# FPGA_0.net
KiCad netlist of a schematic drawn in Altium Designer
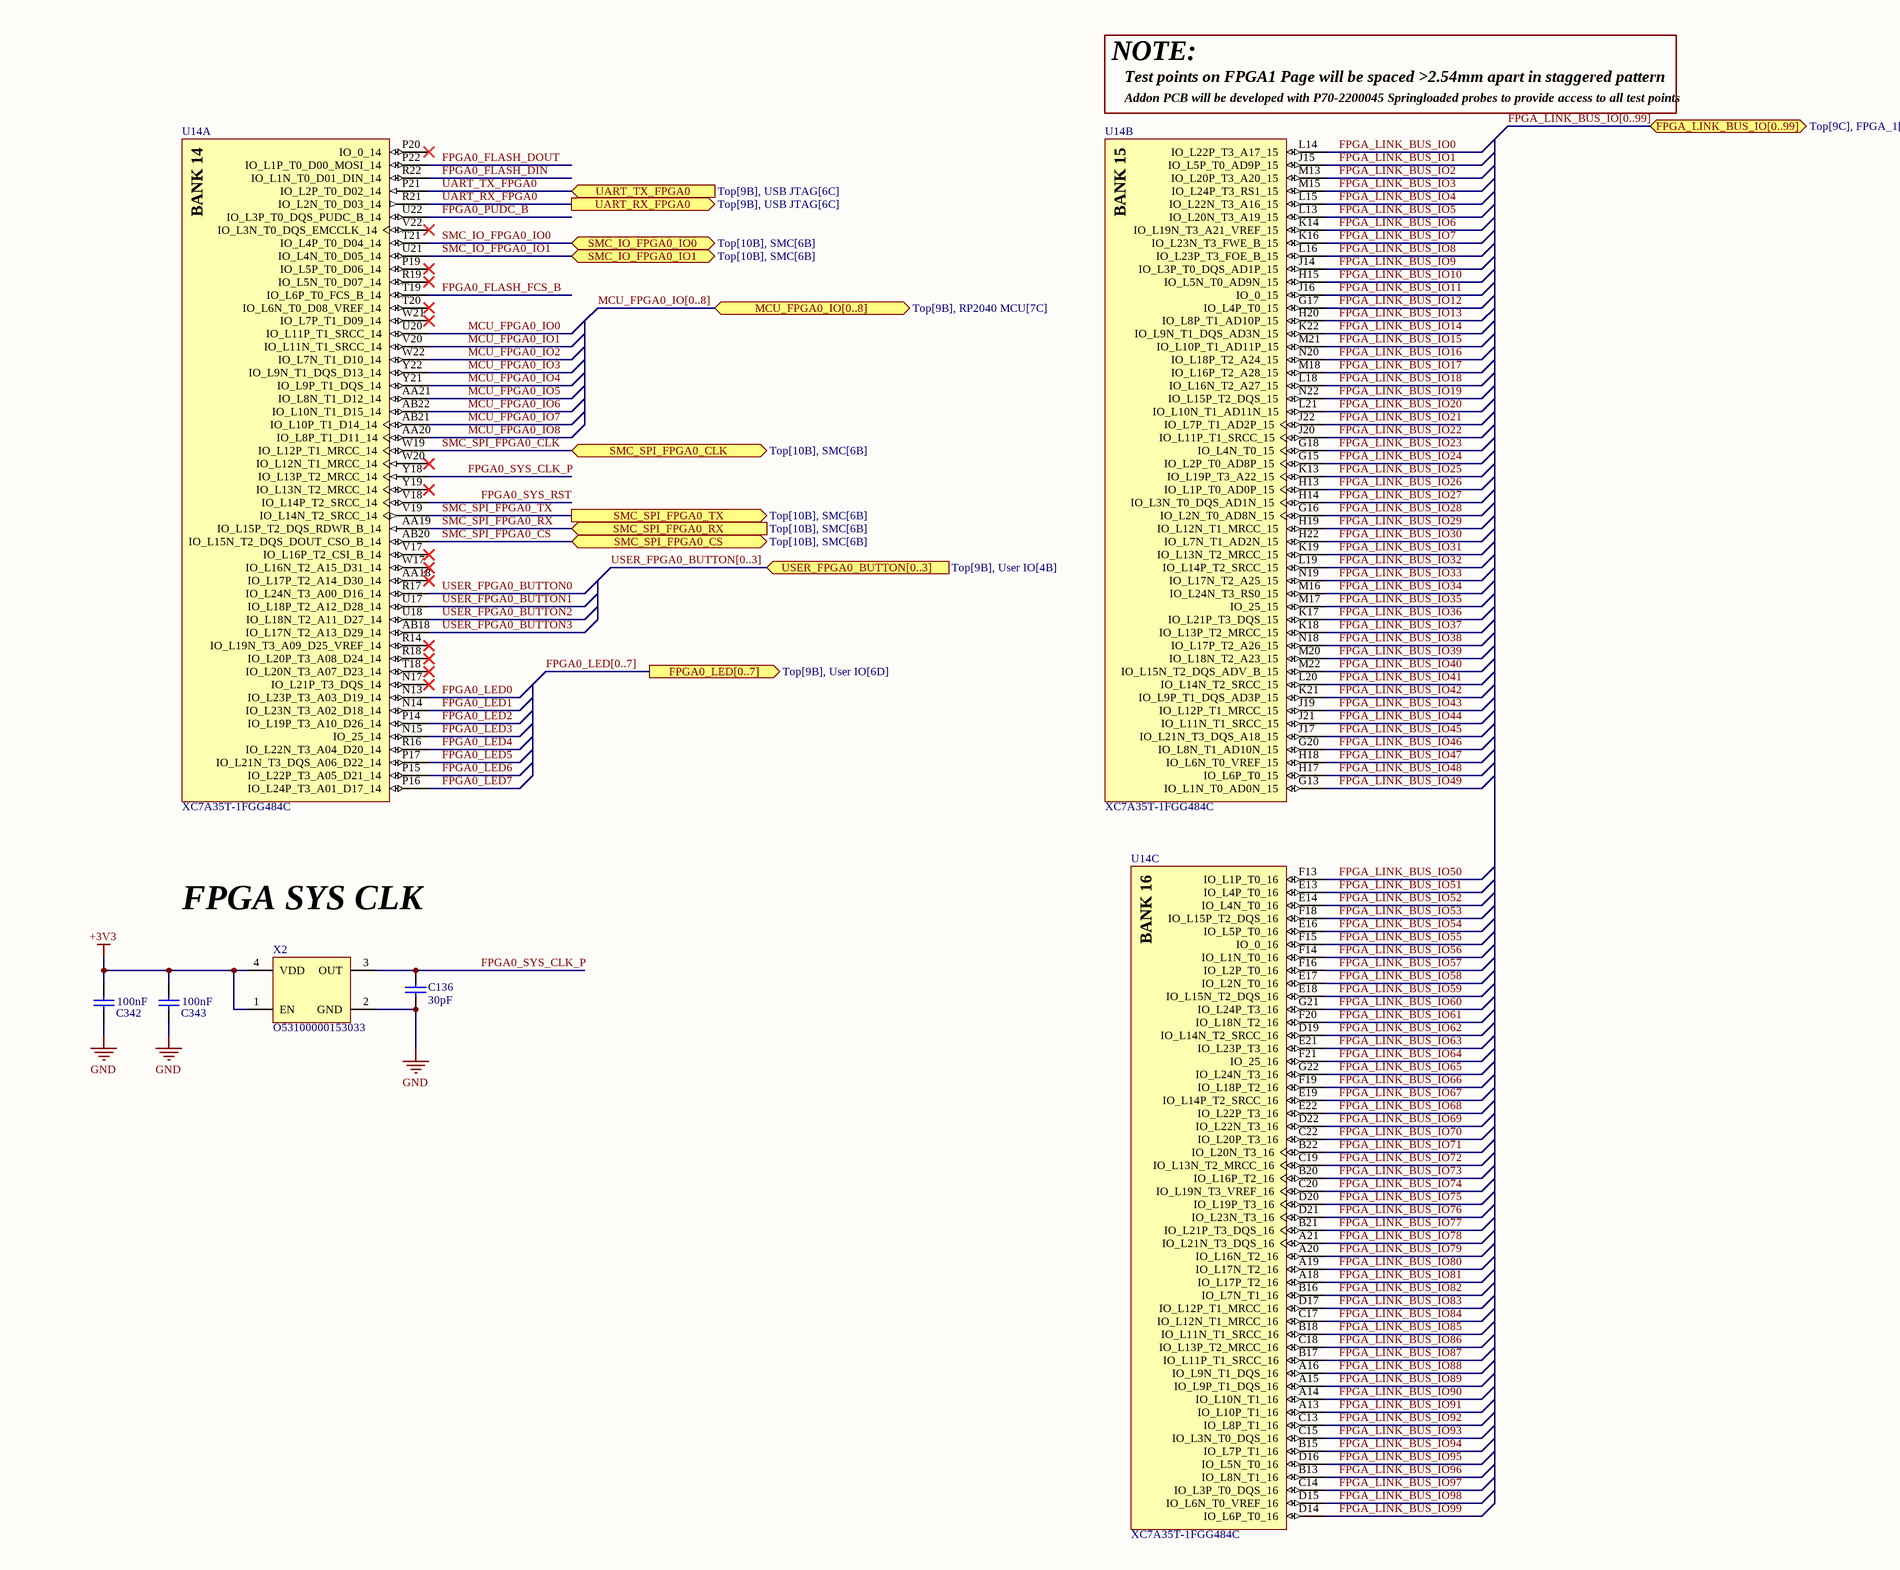
[diagram p0: FPGA_0.SchDoc, top left]
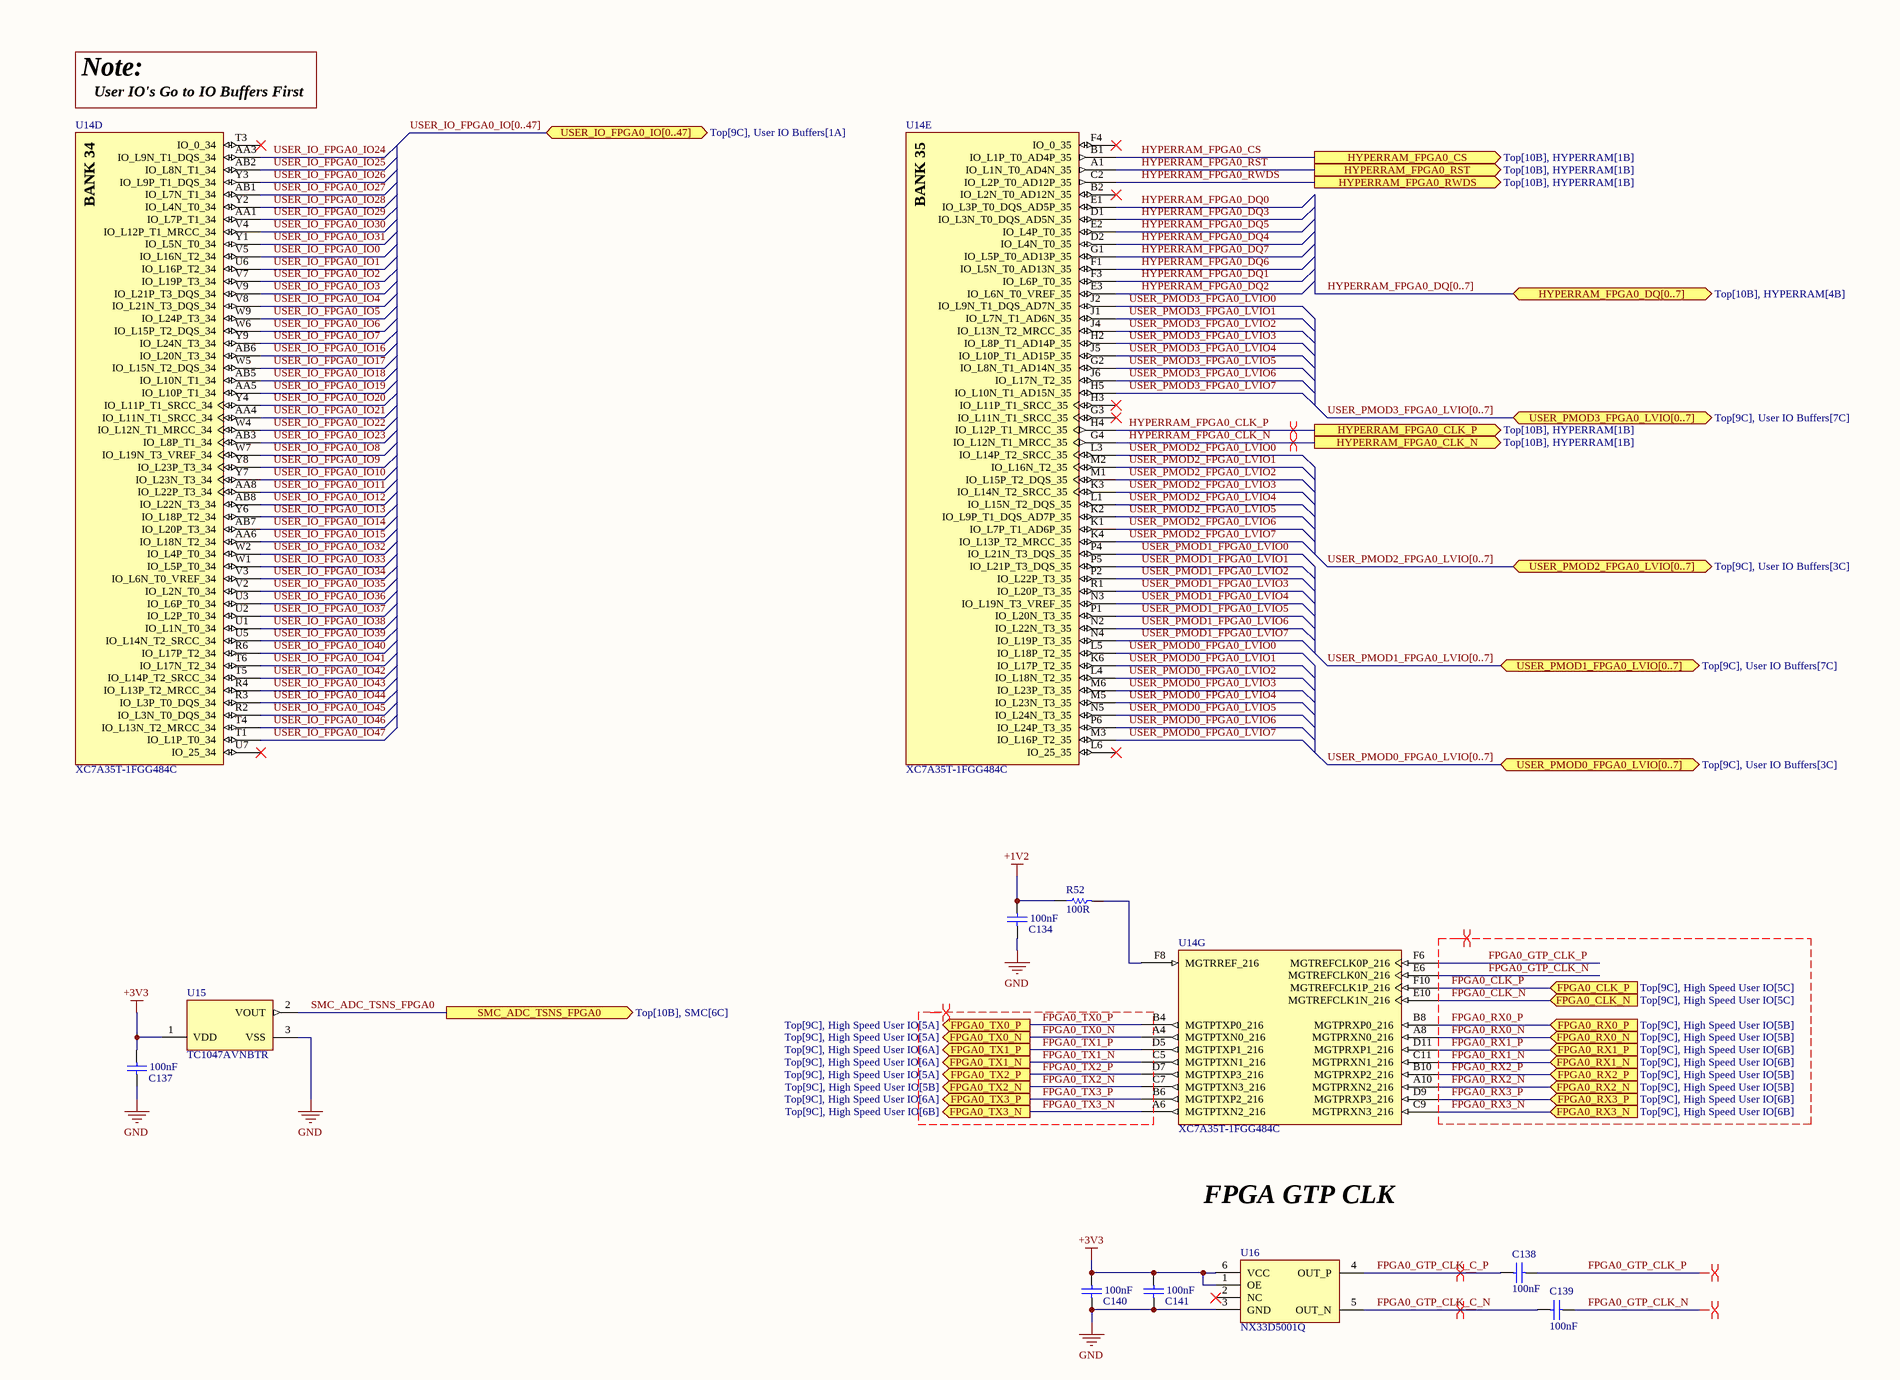
[diagram p1: FPGA_0.SchDoc, top right]
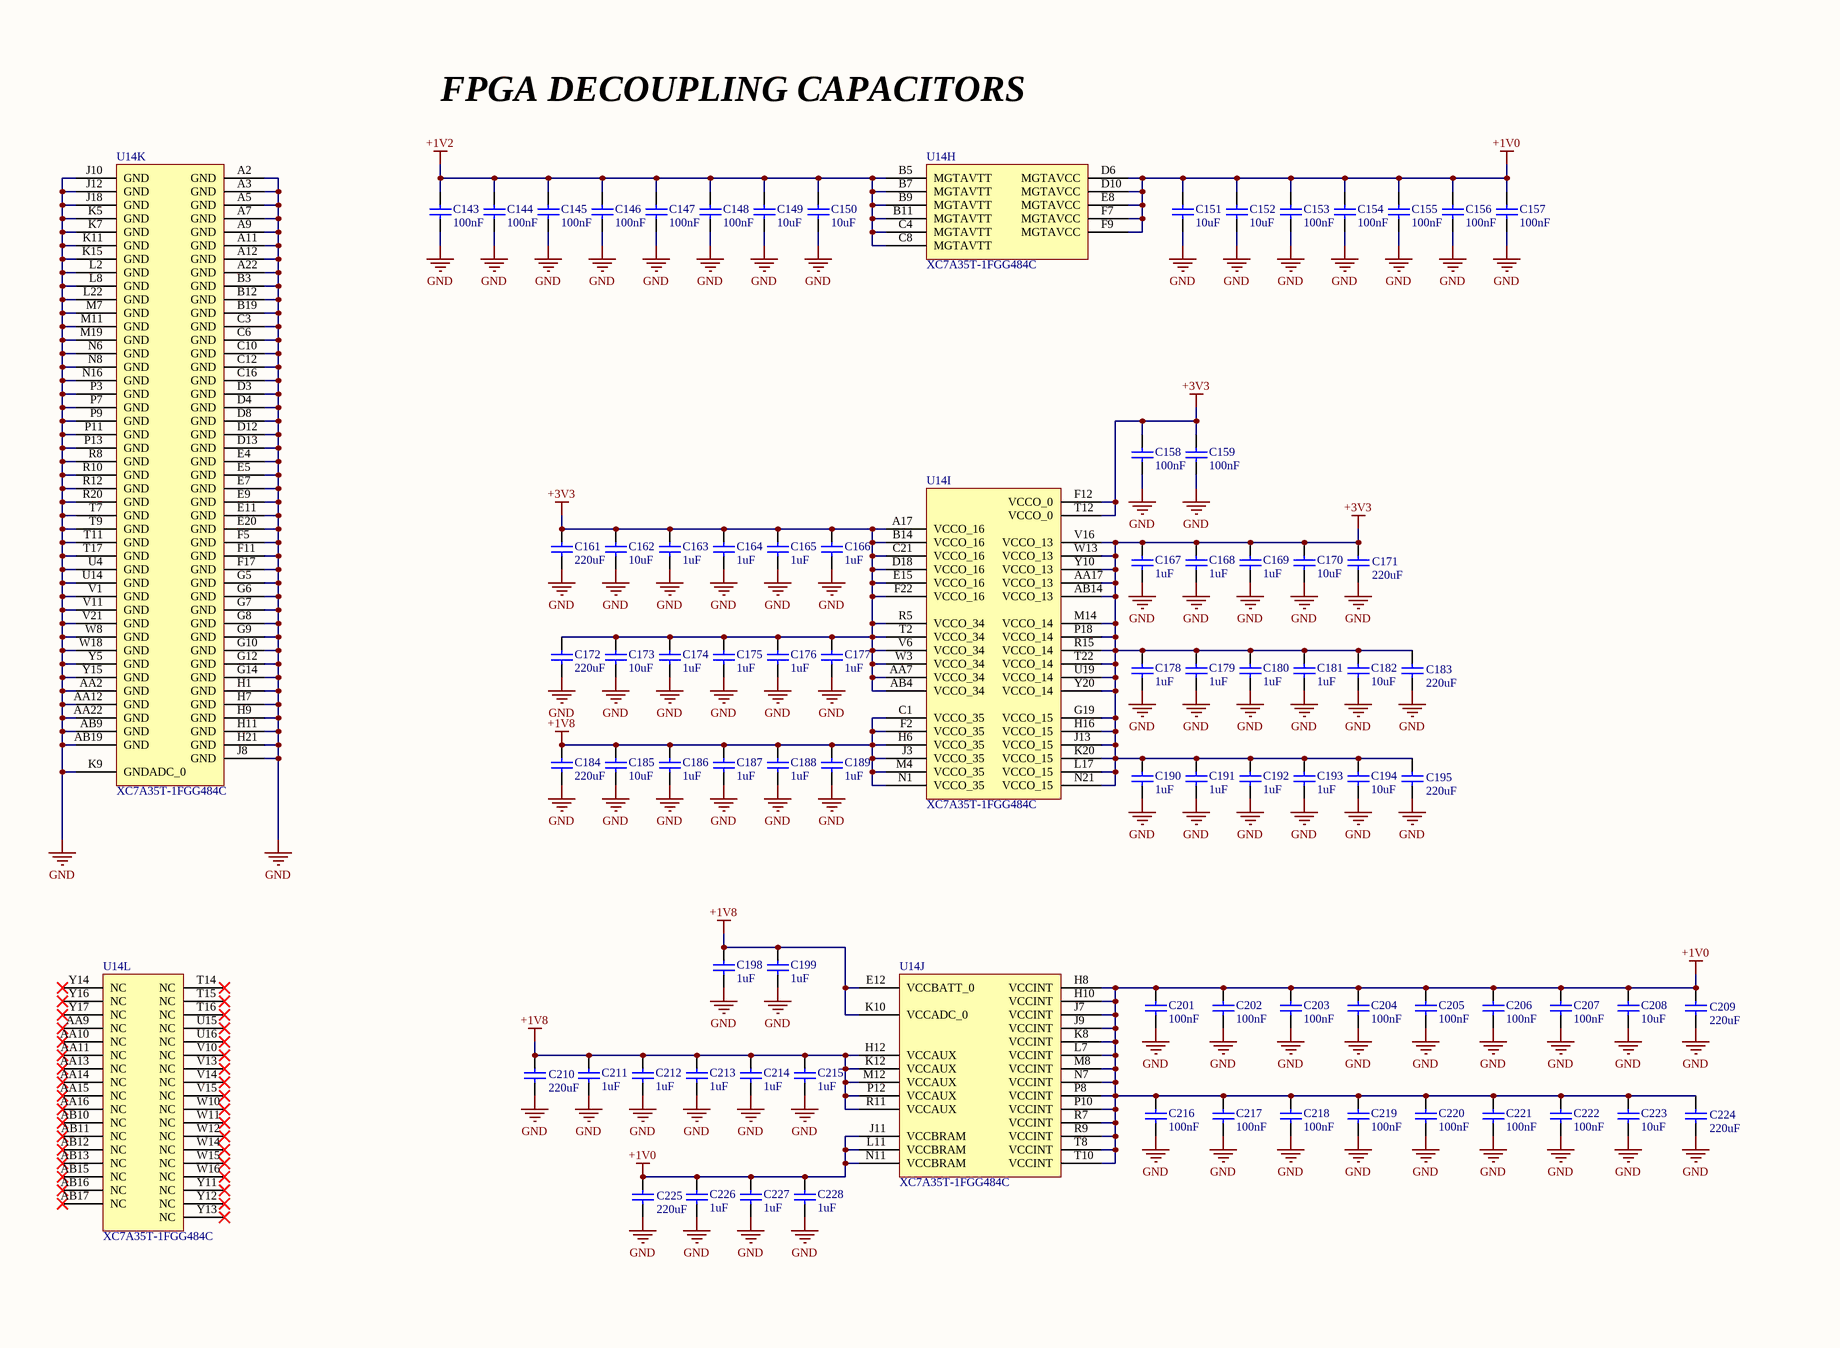
[diagram p2: FPGA_0.SchDoc, bottom left]
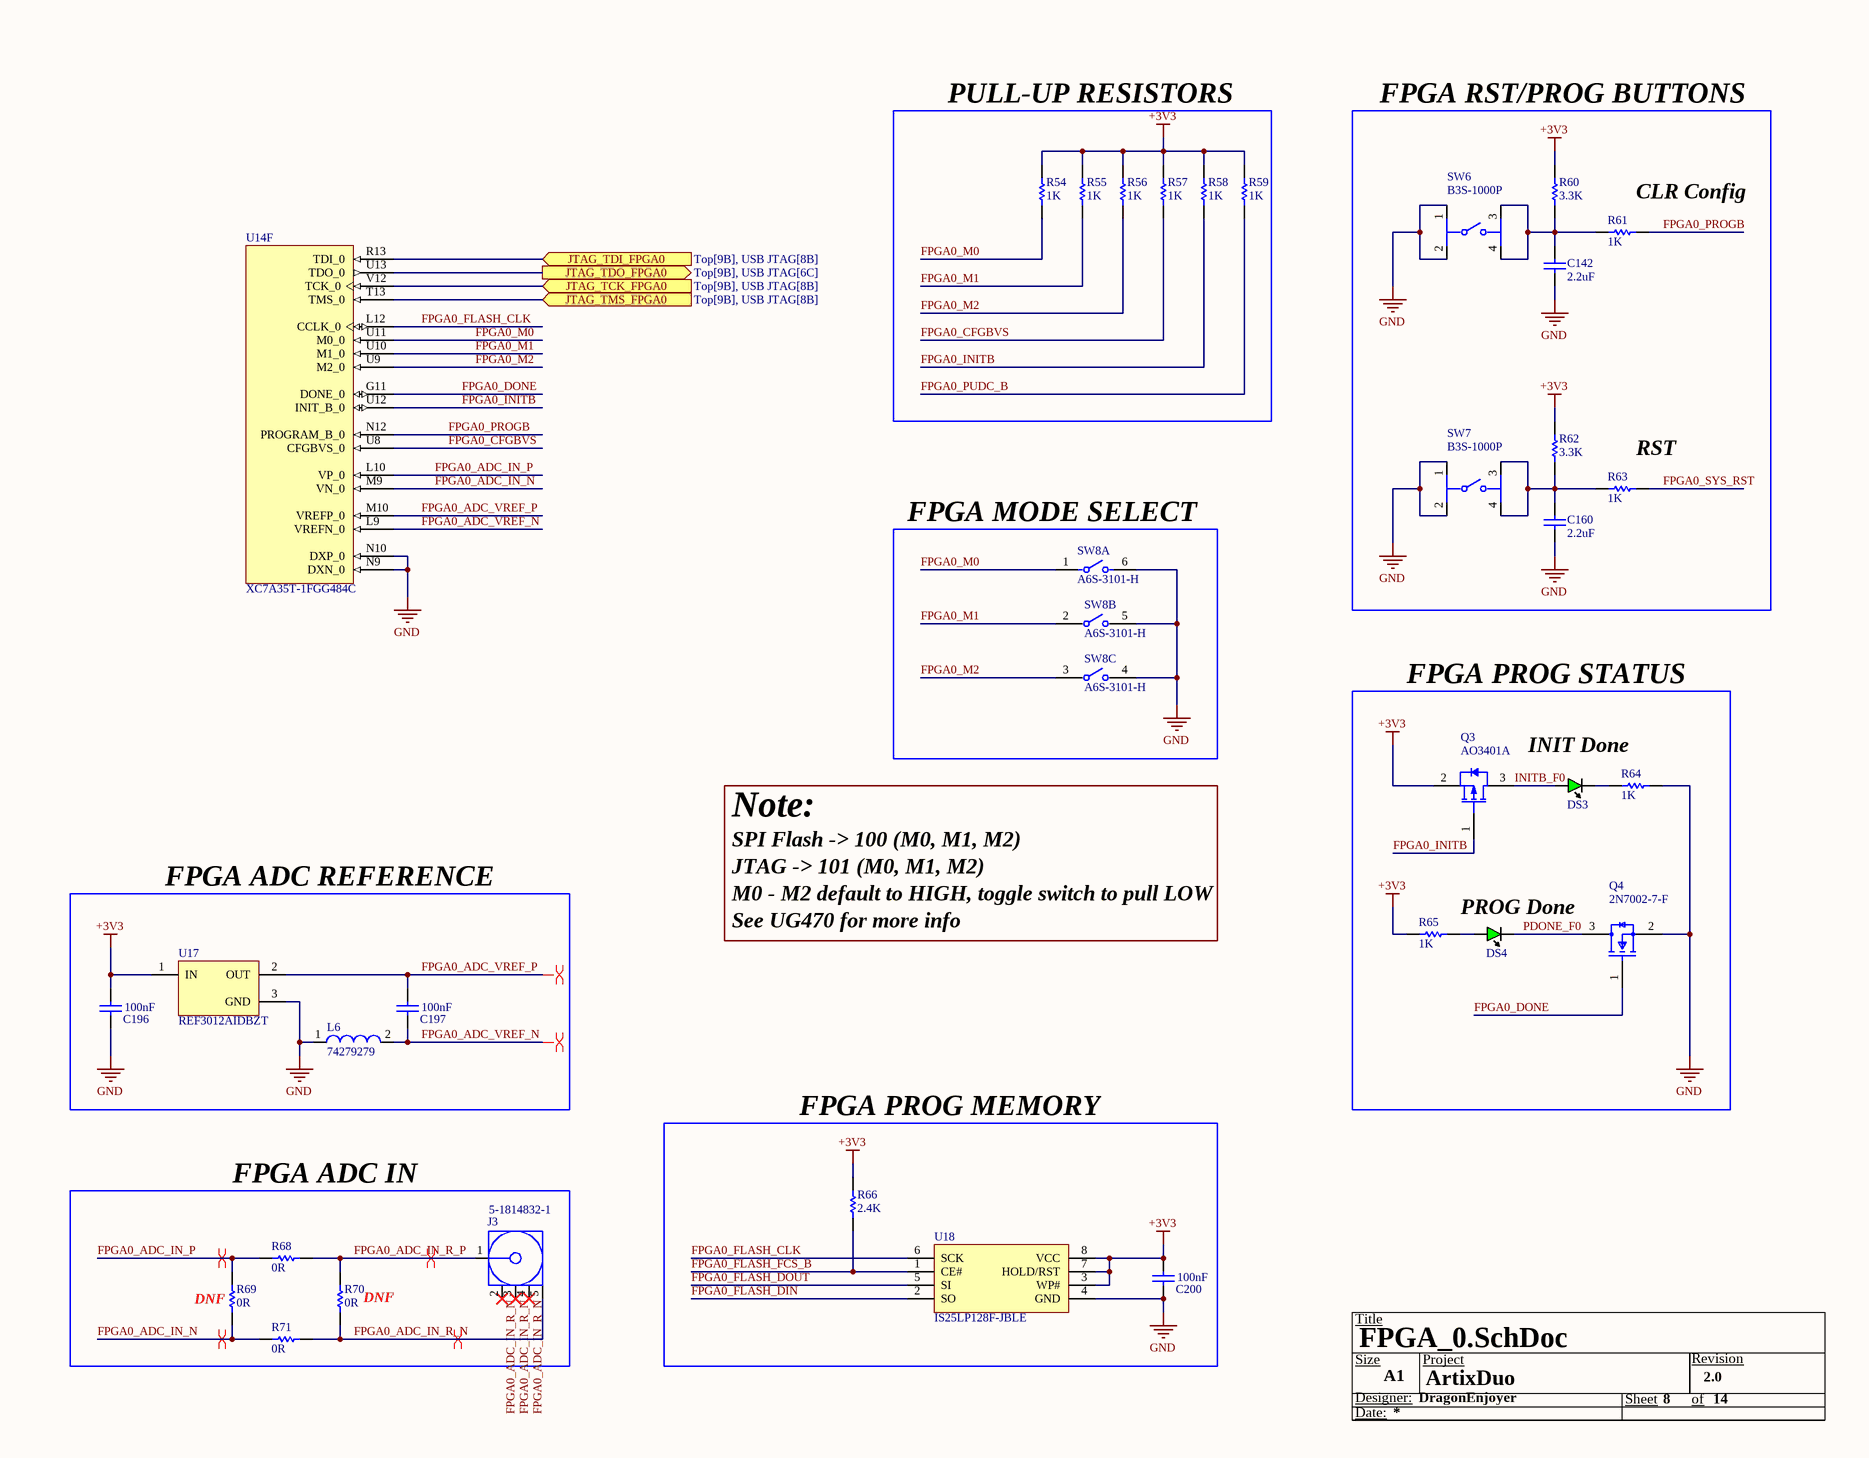
[diagram p3: FPGA_0.SchDoc, bottom right]

(export (version "E")
  (design (tool "Eeschema 10.0.6"))
  (components
    (comp (ref "C134")
      (value "100nF")
      (footprint "CAPC1005X05N")
      (description "Cap Ceramic 0.1uF 50V X7R 20% SMD 0402 125°C Paper T/R GRM155R71H104ME14J")
      (fields (field (name "VOLTAGE") "50V"))
      (libsource (lib "Main Workspace") (part "CAP"))
    )
    (comp (ref "C136")
      (value "30pF")
      (footprint "CAPC1005X56X25NL10T15")
      (description "04025A300JAT2A")
      (fields (field (name "MANUFACTURER") "AVX Interconnect / Elco"))
      (libsource (lib "Altium Content Vault") (part "CAP"))
    )
    (comp (ref "C137")
      (value "100nF")
      (footprint "CAPC1005X05N")
      (description "Cap Ceramic 0.1uF 50V X7R 20% SMD 0402 125°C Paper T/R GRM155R71H104ME14J")
      (fields (field (name "VOLTAGE") "50V"))
      (libsource (lib "Main Workspace") (part "CAP"))
    )
    (comp (ref "C138")
      (value "100nF")
      (footprint "CAPC1005X05N")
      (description "Cap Ceramic 0.1uF 50V X7R 20% SMD 0402 125°C Paper T/R GRM155R71H104ME14J")
      (fields (field (name "VOLTAGE") "50V"))
      (libsource (lib "Main Workspace") (part "CAP"))
    )
    (comp (ref "C139")
      (value "100nF")
      (footprint "CAPC1005X05N")
      (description "Cap Ceramic 0.1uF 50V X7R 20% SMD 0402 125°C Paper T/R GRM155R71H104ME14J")
      (fields (field (name "VOLTAGE") "50V"))
      (libsource (lib "Main Workspace") (part "CAP"))
    )
    (comp (ref "C140")
      (value "100nF")
      (footprint "CAPC1005X05N")
      (description "Cap Ceramic 0.1uF 50V X7R 20% SMD 0402 125°C Paper T/R GRM155R71H104ME14J")
      (fields (field (name "VOLTAGE") "50V"))
      (libsource (lib "Main Workspace") (part "CAP"))
    )
    (comp (ref "C141")
      (value "100nF")
      (footprint "CAPC1005X05N")
      (description "Cap Ceramic 0.1uF 50V X7R 20% SMD 0402 125°C Paper T/R GRM155R71H104ME14J")
      (fields (field (name "VOLTAGE") "50V"))
      (libsource (lib "Main Workspace") (part "CAP"))
    )
    (comp (ref "C142")
      (value "2.2uF")
      (footprint "CAPC1005X55X25NL05T10")
      (description "GRM155R60J225ME15D")
      (fields (field (name "MANUFACTURER") "Murata"))
      (libsource (lib "Altium Content Vault") (part "CAP"))
    )
    (comp (ref "C143")
      (value "100nF")
      (footprint "CAPC1005X05N")
      (description "0402 0.1 uF 25 V ±10% Tolerance X7R SMT Multilayer Ceramic Capacitor")
      (fields (field (name "TOLERANCE") "10%") (field (name "Comment") "GRM155R71E104KE14J"))
      (libsource (lib "Main Workspace") (part "CAP"))
    )
    (comp (ref "C144")
      (value "100nF")
      (footprint "CAPC1005X05N")
      (description "0402 0.1 uF 25 V ±10% Tolerance X7R SMT Multilayer Ceramic Capacitor")
      (fields (field (name "TOLERANCE") "10%") (field (name "Comment") "GRM155R71E104KE14J"))
      (libsource (lib "Main Workspace") (part "CAP"))
    )
    (comp (ref "C145")
      (value "100nF")
      (footprint "CAPC1005X05N")
      (description "0402 0.1 uF 25 V ±10% Tolerance X7R SMT Multilayer Ceramic Capacitor")
      (fields (field (name "TOLERANCE") "10%") (field (name "Comment") "GRM155R71E104KE14J"))
      (libsource (lib "Main Workspace") (part "CAP"))
    )
    (comp (ref "C146")
      (value "100nF")
      (footprint "CAPC1005X05N")
      (description "0402 0.1 uF 25 V ±10% Tolerance X7R SMT Multilayer Ceramic Capacitor")
      (fields (field (name "TOLERANCE") "10%") (field (name "Comment") "GRM155R71E104KE14J"))
      (libsource (lib "Main Workspace") (part "CAP"))
    )
    (comp (ref "C147")
      (value "100nF")
      (footprint "CAPC1005X05N")
      (description "0402 0.1 uF 25 V ±10% Tolerance X7R SMT Multilayer Ceramic Capacitor")
      (fields (field (name "TOLERANCE") "10%") (field (name "Comment") "GRM155R71E104KE14J"))
      (libsource (lib "Main Workspace") (part "CAP"))
    )
    (comp (ref "C148")
      (value "100nF")
      (footprint "CAPC1005X05N")
      (description "0402 0.1 uF 25 V ±10% Tolerance X7R SMT Multilayer Ceramic Capacitor")
      (fields (field (name "TOLERANCE") "10%") (field (name "Comment") "GRM155R71E104KE14J"))
      (libsource (lib "Main Workspace") (part "CAP"))
    )
    (comp (ref "C149")
      (value "10uF")
      (footprint "CAPC1608X05N")
      (description "Cap 10UF 6.3VDC X5R 20% SMD 0603 Paper Tape")
      (fields (field (name "TOLERANCE") "20%") (field (name "Comment") "GRM185R60J106ME15J"))
      (libsource (lib "Main Workspace") (part "CAP"))
    )
    (comp (ref "C150")
      (value "10uF")
      (footprint "CAPC1608X05N")
      (description "Cap 10UF 6.3VDC X5R 20% SMD 0603 Paper Tape")
      (fields (field (name "TOLERANCE") "20%") (field (name "Comment") "GRM185R60J106ME15J"))
      (libsource (lib "Main Workspace") (part "CAP"))
    )
    (comp (ref "C151")
      (value "10uF")
      (footprint "CAPC1608X05N")
      (description "Cap 10UF 6.3VDC X5R 20% SMD 0603 Paper Tape")
      (fields (field (name "TOLERANCE") "20%") (field (name "Comment") "GRM185R60J106ME15J"))
      (libsource (lib "Main Workspace") (part "CAP"))
    )
    (comp (ref "C152")
      (value "10uF")
      (footprint "CAPC1608X05N")
      (description "Cap 10UF 6.3VDC X5R 20% SMD 0603 Paper Tape")
      (fields (field (name "TOLERANCE") "20%") (field (name "Comment") "GRM185R60J106ME15J"))
      (libsource (lib "Main Workspace") (part "CAP"))
    )
    (comp (ref "C153")
      (value "100nF")
      (footprint "CAPC1005X05N")
      (description "0402 0.1 uF 25 V ±10% Tolerance X7R SMT Multilayer Ceramic Capacitor")
      (fields (field (name "TOLERANCE") "10%") (field (name "Comment") "GRM155R71E104KE14J"))
      (libsource (lib "Main Workspace") (part "CAP"))
    )
    (comp (ref "C154")
      (value "100nF")
      (footprint "CAPC1005X05N")
      (description "0402 0.1 uF 25 V ±10% Tolerance X7R SMT Multilayer Ceramic Capacitor")
      (fields (field (name "TOLERANCE") "10%") (field (name "Comment") "GRM155R71E104KE14J"))
      (libsource (lib "Main Workspace") (part "CAP"))
    )
    (comp (ref "C155")
      (value "100nF")
      (footprint "CAPC1005X05N")
      (description "0402 0.1 uF 25 V ±10% Tolerance X7R SMT Multilayer Ceramic Capacitor")
      (fields (field (name "TOLERANCE") "10%") (field (name "Comment") "GRM155R71E104KE14J"))
      (libsource (lib "Main Workspace") (part "CAP"))
    )
    (comp (ref "C156")
      (value "100nF")
      (footprint "CAPC1005X05N")
      (description "0402 0.1 uF 25 V ±10% Tolerance X7R SMT Multilayer Ceramic Capacitor")
      (fields (field (name "TOLERANCE") "10%") (field (name "Comment") "GRM155R71E104KE14J"))
      (libsource (lib "Main Workspace") (part "CAP"))
    )
    (comp (ref "C157")
      (value "100nF")
      (footprint "CAPC1005X05N")
      (description "0402 0.1 uF 25 V ±10% Tolerance X7R SMT Multilayer Ceramic Capacitor")
      (fields (field (name "TOLERANCE") "10%") (field (name "Comment") "GRM155R71E104KE14J"))
      (libsource (lib "Main Workspace") (part "CAP"))
    )
    (comp (ref "C158")
      (value "100nF")
      (footprint "CAPC1005X05N")
      (description "0402 0.1 uF 25 V ±10% Tolerance X7R SMT Multilayer Ceramic Capacitor")
      (fields (field (name "TOLERANCE") "10%") (field (name "Comment") "GRM155R71E104KE14J"))
      (libsource (lib "Main Workspace") (part "CAP"))
    )
    (comp (ref "C159")
      (value "100nF")
      (footprint "CAPC1005X05N")
      (description "0402 0.1 uF 25 V ±10% Tolerance X7R SMT Multilayer Ceramic Capacitor")
      (fields (field (name "TOLERANCE") "10%") (field (name "Comment") "GRM155R71E104KE14J"))
      (libsource (lib "Main Workspace") (part "CAP"))
    )
    (comp (ref "C160")
      (value "2.2uF")
      (footprint "CAPC1005X55X25NL05T10")
      (description "GRM155R60J225ME15D")
      (fields (field (name "MANUFACTURER") "Murata"))
      (libsource (lib "Altium Content Vault") (part "CAP"))
    )
    (comp (ref "C161")
      (value "220uF")
      (footprint "CAPC3225X25N")
      (description "Cap Ceramic 220uF 6.3V X5R 20% SMD 1210 85°C Emboss T/R GRM32ER60J227ME05K")
      (libsource (lib "Main Workspace") (part "CAP"))
    )
    (comp (ref "C162")
      (value "10uF")
      (footprint "CAPC1608X05N")
      (description "Cap 10UF 6.3VDC X5R 20% SMD 0603 Paper Tape")
      (fields (field (name "TOLERANCE") "20%") (field (name "Comment") "GRM185R60J106ME15J"))
      (libsource (lib "Main Workspace") (part "CAP"))
    )
    (comp (ref "C163")
      (value "1uF")
      (footprint "CAPC1005X05N")
      (fields (field (name "TOLERANCE") "20%") (field (name "Comment") "GRM153R61A105ME95D"))
      (libsource (lib "Main Workspace") (part "CAP"))
    )
    (comp (ref "C164")
      (value "1uF")
      (footprint "CAPC1005X05N")
      (fields (field (name "TOLERANCE") "20%") (field (name "Comment") "GRM153R61A105ME95D"))
      (libsource (lib "Main Workspace") (part "CAP"))
    )
    (comp (ref "C165")
      (value "1uF")
      (footprint "CAPC1005X05N")
      (fields (field (name "TOLERANCE") "20%") (field (name "Comment") "GRM153R61A105ME95D"))
      (libsource (lib "Main Workspace") (part "CAP"))
    )
    (comp (ref "C166")
      (value "1uF")
      (footprint "CAPC1005X05N")
      (fields (field (name "TOLERANCE") "20%") (field (name "Comment") "GRM153R61A105ME95D"))
      (libsource (lib "Main Workspace") (part "CAP"))
    )
    (comp (ref "C167")
      (value "1uF")
      (footprint "CAPC1005X05N")
      (fields (field (name "TOLERANCE") "20%") (field (name "Comment") "GRM153R61A105ME95D"))
      (libsource (lib "Main Workspace") (part "CAP"))
    )
    (comp (ref "C168")
      (value "1uF")
      (footprint "CAPC1005X05N")
      (fields (field (name "TOLERANCE") "20%") (field (name "Comment") "GRM153R61A105ME95D"))
      (libsource (lib "Main Workspace") (part "CAP"))
    )
    (comp (ref "C169")
      (value "1uF")
      (footprint "CAPC1005X05N")
      (fields (field (name "TOLERANCE") "20%") (field (name "Comment") "GRM153R61A105ME95D"))
      (libsource (lib "Main Workspace") (part "CAP"))
    )
    (comp (ref "C170")
      (value "10uF")
      (footprint "CAPC1608X05N")
      (description "Cap 10UF 6.3VDC X5R 20% SMD 0603 Paper Tape")
      (fields (field (name "TOLERANCE") "20%") (field (name "Comment") "GRM185R60J106ME15J"))
      (libsource (lib "Main Workspace") (part "CAP"))
    )
    (comp (ref "C171")
      (value "220uF")
      (footprint "CAPC3225X25N")
      (description "Cap Ceramic 220uF 6.3V X5R 20% SMD 1210 85°C Emboss T/R GRM32ER60J227ME05K")
      (libsource (lib "Main Workspace") (part "CAP"))
    )
    (comp (ref "C172")
      (value "220uF")
      (footprint "CAPC3225X25N")
      (description "Cap Ceramic 220uF 6.3V X5R 20% SMD 1210 85°C Emboss T/R GRM32ER60J227ME05K")
      (libsource (lib "Main Workspace") (part "CAP"))
    )
    (comp (ref "C173")
      (value "10uF")
      (footprint "CAPC1608X05N")
      (description "Cap 10UF 6.3VDC X5R 20% SMD 0603 Paper Tape")
      (fields (field (name "TOLERANCE") "20%") (field (name "Comment") "GRM185R60J106ME15J"))
      (libsource (lib "Main Workspace") (part "CAP"))
    )
    (comp (ref "C174")
      (value "1uF")
      (footprint "CAPC1005X05N")
      (fields (field (name "TOLERANCE") "20%") (field (name "Comment") "GRM153R61A105ME95D"))
      (libsource (lib "Main Workspace") (part "CAP"))
    )
    (comp (ref "C175")
      (value "1uF")
      (footprint "CAPC1005X05N")
      (fields (field (name "TOLERANCE") "20%") (field (name "Comment") "GRM153R61A105ME95D"))
      (libsource (lib "Main Workspace") (part "CAP"))
    )
    (comp (ref "C176")
      (value "1uF")
      (footprint "CAPC1005X05N")
      (fields (field (name "TOLERANCE") "20%") (field (name "Comment") "GRM153R61A105ME95D"))
      (libsource (lib "Main Workspace") (part "CAP"))
    )
    (comp (ref "C177")
      (value "1uF")
      (footprint "CAPC1005X05N")
      (fields (field (name "TOLERANCE") "20%") (field (name "Comment") "GRM153R61A105ME95D"))
      (libsource (lib "Main Workspace") (part "CAP"))
    )
    (comp (ref "C178")
      (value "1uF")
      (footprint "CAPC1005X05N")
      (fields (field (name "TOLERANCE") "20%") (field (name "Comment") "GRM153R61A105ME95D"))
      (libsource (lib "Main Workspace") (part "CAP"))
    )
    (comp (ref "C179")
      (value "1uF")
      (footprint "CAPC1005X05N")
      (fields (field (name "TOLERANCE") "20%") (field (name "Comment") "GRM153R61A105ME95D"))
      (libsource (lib "Main Workspace") (part "CAP"))
    )
    (comp (ref "C180")
      (value "1uF")
      (footprint "CAPC1005X05N")
      (fields (field (name "TOLERANCE") "20%") (field (name "Comment") "GRM153R61A105ME95D"))
      (libsource (lib "Main Workspace") (part "CAP"))
    )
    (comp (ref "C181")
      (value "1uF")
      (footprint "CAPC1005X05N")
      (fields (field (name "TOLERANCE") "20%") (field (name "Comment") "GRM153R61A105ME95D"))
      (libsource (lib "Main Workspace") (part "CAP"))
    )
    (comp (ref "C182")
      (value "10uF")
      (footprint "CAPC1608X05N")
      (description "Cap 10UF 6.3VDC X5R 20% SMD 0603 Paper Tape")
      (fields (field (name "TOLERANCE") "20%") (field (name "Comment") "GRM185R60J106ME15J"))
      (libsource (lib "Main Workspace") (part "CAP"))
    )
    (comp (ref "C183")
      (value "220uF")
      (footprint "CAPC3225X25N")
      (description "Cap Ceramic 220uF 6.3V X5R 20% SMD 1210 85°C Emboss T/R GRM32ER60J227ME05K")
      (libsource (lib "Main Workspace") (part "CAP"))
    )
    (comp (ref "C184")
      (value "220uF")
      (footprint "CAPC3225X25N")
      (description "Cap Ceramic 220uF 6.3V X5R 20% SMD 1210 85°C Emboss T/R GRM32ER60J227ME05K")
      (libsource (lib "Main Workspace") (part "CAP"))
    )
    (comp (ref "C185")
      (value "10uF")
      (footprint "CAPC1608X05N")
      (description "Cap 10UF 6.3VDC X5R 20% SMD 0603 Paper Tape")
      (fields (field (name "TOLERANCE") "20%") (field (name "Comment") "GRM185R60J106ME15J"))
      (libsource (lib "Main Workspace") (part "CAP"))
    )
    (comp (ref "C186")
      (value "1uF")
      (footprint "CAPC1005X05N")
      (fields (field (name "TOLERANCE") "20%") (field (name "Comment") "GRM153R61A105ME95D"))
      (libsource (lib "Main Workspace") (part "CAP"))
    )
    (comp (ref "C187")
      (value "1uF")
      (footprint "CAPC1005X05N")
      (fields (field (name "TOLERANCE") "20%") (field (name "Comment") "GRM153R61A105ME95D"))
      (libsource (lib "Main Workspace") (part "CAP"))
    )
    (comp (ref "C188")
      (value "1uF")
      (footprint "CAPC1005X05N")
      (fields (field (name "TOLERANCE") "20%") (field (name "Comment") "GRM153R61A105ME95D"))
      (libsource (lib "Main Workspace") (part "CAP"))
    )
    (comp (ref "C189")
      (value "1uF")
      (footprint "CAPC1005X05N")
      (fields (field (name "TOLERANCE") "20%") (field (name "Comment") "GRM153R61A105ME95D"))
      (libsource (lib "Main Workspace") (part "CAP"))
    )
    (comp (ref "C190")
      (value "1uF")
      (footprint "CAPC1005X05N")
      (fields (field (name "TOLERANCE") "20%") (field (name "Comment") "GRM153R61A105ME95D"))
      (libsource (lib "Main Workspace") (part "CAP"))
    )
    (comp (ref "C191")
      (value "1uF")
      (footprint "CAPC1005X05N")
      (fields (field (name "TOLERANCE") "20%") (field (name "Comment") "GRM153R61A105ME95D"))
      (libsource (lib "Main Workspace") (part "CAP"))
    )
    (comp (ref "C192")
      (value "1uF")
      (footprint "CAPC1005X05N")
      (fields (field (name "TOLERANCE") "20%") (field (name "Comment") "GRM153R61A105ME95D"))
      (libsource (lib "Main Workspace") (part "CAP"))
    )
    (comp (ref "C193")
      (value "1uF")
      (footprint "CAPC1005X05N")
      (fields (field (name "TOLERANCE") "20%") (field (name "Comment") "GRM153R61A105ME95D"))
      (libsource (lib "Main Workspace") (part "CAP"))
    )
    (comp (ref "C194")
      (value "10uF")
      (footprint "CAPC1608X05N")
      (description "Cap 10UF 6.3VDC X5R 20% SMD 0603 Paper Tape")
      (fields (field (name "TOLERANCE") "20%") (field (name "Comment") "GRM185R60J106ME15J"))
      (libsource (lib "Main Workspace") (part "CAP"))
    )
    (comp (ref "C195")
      (value "220uF")
      (footprint "CAPC3225X25N")
      (description "Cap Ceramic 220uF 6.3V X5R 20% SMD 1210 85°C Emboss T/R GRM32ER60J227ME05K")
      (libsource (lib "Main Workspace") (part "CAP"))
    )
    (comp (ref "C196")
      (value "100nF")
      (footprint "CAPC1005X05N")
      (description "Cap Ceramic 0.1uF 50V X7R 20% SMD 0402 125°C Paper T/R GRM155R71H104ME14J")
      (fields (field (name "VOLTAGE") "50V"))
      (libsource (lib "Main Workspace") (part "CAP"))
    )
    (comp (ref "C197")
      (value "100nF")
      (footprint "CAPC1005X05N")
      (description "Cap Ceramic 0.1uF 50V X7R 20% SMD 0402 125°C Paper T/R GRM155R71H104ME14J")
      (fields (field (name "VOLTAGE") "50V"))
      (libsource (lib "Main Workspace") (part "CAP"))
    )
    (comp (ref "C198")
      (value "1uF")
      (footprint "CAPC1005X05N")
      (fields (field (name "TOLERANCE") "20%") (field (name "Comment") "GRM153R61A105ME95D"))
      (libsource (lib "Main Workspace") (part "CAP"))
    )
    (comp (ref "C199")
      (value "1uF")
      (footprint "CAPC1005X05N")
      (fields (field (name "TOLERANCE") "20%") (field (name "Comment") "GRM153R61A105ME95D"))
      (libsource (lib "Main Workspace") (part "CAP"))
    )
    (comp (ref "C200")
      (value "100nF")
      (footprint "CAPC1005X05N")
      (description "Cap Ceramic 0.1uF 50V X7R 20% SMD 0402 125°C Paper T/R GRM155R71H104ME14J")
      (fields (field (name "VOLTAGE") "50V"))
      (libsource (lib "Main Workspace") (part "CAP"))
    )
    (comp (ref "C201")
      (value "100nF")
      (footprint "CAPC1005X05N")
      (description "0402 0.1 uF 25 V ±10% Tolerance X7R SMT Multilayer Ceramic Capacitor")
      (fields (field (name "TOLERANCE") "10%") (field (name "Comment") "GRM155R71E104KE14J"))
      (libsource (lib "Main Workspace") (part "CAP"))
    )
    (comp (ref "C202")
      (value "100nF")
      (footprint "CAPC1005X05N")
      (description "0402 0.1 uF 25 V ±10% Tolerance X7R SMT Multilayer Ceramic Capacitor")
      (fields (field (name "TOLERANCE") "10%") (field (name "Comment") "GRM155R71E104KE14J"))
      (libsource (lib "Main Workspace") (part "CAP"))
    )
    (comp (ref "C203")
      (value "100nF")
      (footprint "CAPC1005X05N")
      (description "0402 0.1 uF 25 V ±10% Tolerance X7R SMT Multilayer Ceramic Capacitor")
      (fields (field (name "TOLERANCE") "10%") (field (name "Comment") "GRM155R71E104KE14J"))
      (libsource (lib "Main Workspace") (part "CAP"))
    )
    (comp (ref "C204")
      (value "100nF")
      (footprint "CAPC1005X05N")
      (description "0402 0.1 uF 25 V ±10% Tolerance X7R SMT Multilayer Ceramic Capacitor")
      (fields (field (name "TOLERANCE") "10%") (field (name "Comment") "GRM155R71E104KE14J"))
      (libsource (lib "Main Workspace") (part "CAP"))
    )
    (comp (ref "C205")
      (value "100nF")
      (footprint "CAPC1005X05N")
      (description "0402 0.1 uF 25 V ±10% Tolerance X7R SMT Multilayer Ceramic Capacitor")
      (fields (field (name "TOLERANCE") "10%") (field (name "Comment") "GRM155R71E104KE14J"))
      (libsource (lib "Main Workspace") (part "CAP"))
    )
    (comp (ref "C206")
      (value "100nF")
      (footprint "CAPC1005X05N")
      (description "0402 0.1 uF 25 V ±10% Tolerance X7R SMT Multilayer Ceramic Capacitor")
      (fields (field (name "TOLERANCE") "10%") (field (name "Comment") "GRM155R71E104KE14J"))
      (libsource (lib "Main Workspace") (part "CAP"))
    )
    (comp (ref "C207")
      (value "100nF")
      (footprint "CAPC1005X05N")
      (description "0402 0.1 uF 25 V ±10% Tolerance X7R SMT Multilayer Ceramic Capacitor")
      (fields (field (name "TOLERANCE") "10%") (field (name "Comment") "GRM155R71E104KE14J"))
      (libsource (lib "Main Workspace") (part "CAP"))
    )
    (comp (ref "C208")
      (value "10uF")
      (footprint "CAPC1608X05N")
      (description "Cap 10UF 6.3VDC X5R 20% SMD 0603 Paper Tape")
      (fields (field (name "TOLERANCE") "20%") (field (name "Comment") "GRM185R60J106ME15J"))
      (libsource (lib "Main Workspace") (part "CAP"))
    )
    (comp (ref "C209")
      (value "220uF")
      (footprint "CAPC3225X25N")
      (description "Cap Ceramic 220uF 6.3V X5R 20% SMD 1210 85°C Emboss T/R GRM32ER60J227ME05K")
      (libsource (lib "Main Workspace") (part "CAP"))
    )
    (comp (ref "C210")
      (value "220uF")
      (footprint "CAPC3225X25N")
      (description "Cap Ceramic 220uF 6.3V X5R 20% SMD 1210 85°C Emboss T/R GRM32ER60J227ME05K")
      (libsource (lib "Main Workspace") (part "CAP"))
    )
    (comp (ref "C211")
      (value "1uF")
      (footprint "CAPC1005X05N")
      (fields (field (name "TOLERANCE") "20%") (field (name "Comment") "GRM153R61A105ME95D"))
      (libsource (lib "Main Workspace") (part "CAP"))
    )
    (comp (ref "C212")
      (value "1uF")
      (footprint "CAPC1005X05N")
      (fields (field (name "TOLERANCE") "20%") (field (name "Comment") "GRM153R61A105ME95D"))
      (libsource (lib "Main Workspace") (part "CAP"))
    )
    (comp (ref "C213")
      (value "1uF")
      (footprint "CAPC1005X05N")
      (fields (field (name "TOLERANCE") "20%") (field (name "Comment") "GRM153R61A105ME95D"))
      (libsource (lib "Main Workspace") (part "CAP"))
    )
    (comp (ref "C214")
      (value "1uF")
      (footprint "CAPC1005X05N")
      (fields (field (name "TOLERANCE") "20%") (field (name "Comment") "GRM153R61A105ME95D"))
      (libsource (lib "Main Workspace") (part "CAP"))
    )
    (comp (ref "C215")
      (value "1uF")
      (footprint "CAPC1005X05N")
      (fields (field (name "TOLERANCE") "20%") (field (name "Comment") "GRM153R61A105ME95D"))
      (libsource (lib "Main Workspace") (part "CAP"))
    )
    (comp (ref "C216")
      (value "100nF")
      (footprint "CAPC1005X05N")
      (description "0402 0.1 uF 25 V ±10% Tolerance X7R SMT Multilayer Ceramic Capacitor")
      (fields (field (name "TOLERANCE") "10%") (field (name "Comment") "GRM155R71E104KE14J"))
      (libsource (lib "Main Workspace") (part "CAP"))
    )
    (comp (ref "C217")
      (value "100nF")
      (footprint "CAPC1005X05N")
      (description "0402 0.1 uF 25 V ±10% Tolerance X7R SMT Multilayer Ceramic Capacitor")
      (fields (field (name "TOLERANCE") "10%") (field (name "Comment") "GRM155R71E104KE14J"))
      (libsource (lib "Main Workspace") (part "CAP"))
    )
    (comp (ref "C218")
      (value "100nF")
      (footprint "CAPC1005X05N")
      (description "0402 0.1 uF 25 V ±10% Tolerance X7R SMT Multilayer Ceramic Capacitor")
      (fields (field (name "TOLERANCE") "10%") (field (name "Comment") "GRM155R71E104KE14J"))
      (libsource (lib "Main Workspace") (part "CAP"))
    )
    (comp (ref "C219")
      (value "100nF")
      (footprint "CAPC1005X05N")
      (description "0402 0.1 uF 25 V ±10% Tolerance X7R SMT Multilayer Ceramic Capacitor")
      (fields (field (name "TOLERANCE") "10%") (field (name "Comment") "GRM155R71E104KE14J"))
      (libsource (lib "Main Workspace") (part "CAP"))
    )
    (comp (ref "C220")
      (value "100nF")
      (footprint "CAPC1005X05N")
      (description "0402 0.1 uF 25 V ±10% Tolerance X7R SMT Multilayer Ceramic Capacitor")
      (fields (field (name "TOLERANCE") "10%") (field (name "Comment") "GRM155R71E104KE14J"))
      (libsource (lib "Main Workspace") (part "CAP"))
    )
    (comp (ref "C221")
      (value "100nF")
      (footprint "CAPC1005X05N")
      (description "0402 0.1 uF 25 V ±10% Tolerance X7R SMT Multilayer Ceramic Capacitor")
      (fields (field (name "TOLERANCE") "10%") (field (name "Comment") "GRM155R71E104KE14J"))
      (libsource (lib "Main Workspace") (part "CAP"))
    )
    (comp (ref "C222")
      (value "100nF")
      (footprint "CAPC1005X05N")
      (description "0402 0.1 uF 25 V ±10% Tolerance X7R SMT Multilayer Ceramic Capacitor")
      (fields (field (name "TOLERANCE") "10%") (field (name "Comment") "GRM155R71E104KE14J"))
      (libsource (lib "Main Workspace") (part "CAP"))
    )
    (comp (ref "C223")
      (value "10uF")
      (footprint "CAPC1608X05N")
      (description "Cap 10UF 6.3VDC X5R 20% SMD 0603 Paper Tape")
      (fields (field (name "TOLERANCE") "20%") (field (name "Comment") "GRM185R60J106ME15J"))
      (libsource (lib "Main Workspace") (part "CAP"))
    )
    (comp (ref "C224")
      (value "220uF")
      (footprint "CAPC3225X25N")
      (description "Cap Ceramic 220uF 6.3V X5R 20% SMD 1210 85°C Emboss T/R GRM32ER60J227ME05K")
      (libsource (lib "Main Workspace") (part "CAP"))
    )
    (comp (ref "C225")
      (value "220uF")
      (footprint "CAPC3225X25N")
      (description "Cap Ceramic 220uF 6.3V X5R 20% SMD 1210 85°C Emboss T/R GRM32ER60J227ME05K")
      (libsource (lib "Main Workspace") (part "CAP"))
    )
    (comp (ref "C226")
      (value "1uF")
      (footprint "CAPC1005X05N")
      (fields (field (name "TOLERANCE") "20%") (field (name "Comment") "GRM153R61A105ME95D"))
      (libsource (lib "Main Workspace") (part "CAP"))
    )
    (comp (ref "C227")
      (value "1uF")
      (footprint "CAPC1005X05N")
      (fields (field (name "TOLERANCE") "20%") (field (name "Comment") "GRM153R61A105ME95D"))
      (libsource (lib "Main Workspace") (part "CAP"))
    )
    (comp (ref "C228")
      (value "1uF")
      (footprint "CAPC1005X05N")
      (fields (field (name "TOLERANCE") "20%") (field (name "Comment") "GRM153R61A105ME95D"))
      (libsource (lib "Main Workspace") (part "CAP"))
    )
    (comp (ref "C342")
      (value "100nF")
      (footprint "CAPC1005X05N")
      (description "Cap Ceramic 0.1uF 50V X7R 20% SMD 0402 125°C Paper T/R GRM155R71H104ME14J")
      (fields (field (name "VOLTAGE") "50V"))
      (libsource (lib "Main Workspace") (part "CAP"))
    )
    (comp (ref "C343")
      (value "100nF")
      (footprint "CAPC1005X05N")
      (description "Cap Ceramic 0.1uF 50V X7R 20% SMD 0402 125°C Paper T/R GRM155R71H104ME14J")
      (fields (field (name "VOLTAGE") "50V"))
      (libsource (lib "Main Workspace") (part "CAP"))
    )
    (comp (ref "DS3")
      (value "SMLLX0603GWTR")
      (footprint "LUMX-SML-LX0603_V")
      (description "LED GREEN DIFFUSED SMD")
      (libsource (lib "Main Workspace") (part "LED-GREEN-AK-2"))
    )
    (comp (ref "DS4")
      (value "SMLLX0603GWTR")
      (footprint "LUMX-SML-LX0603_V")
      (description "LED GREEN DIFFUSED SMD")
      (libsource (lib "Main Workspace") (part "LED-GREEN-AK-2"))
    )
    (comp (ref "J3")
      (value "5-1814832-1")
      (footprint "TECO-5-1814832-1_V")
      (fields (field (name "MANUFACTURER") "TE Connectivity"))
      (libsource (lib "Altium Content Vault") (part "CN-S-4F-RF5"))
    )
    (comp (ref "L6")
      (value "74279279")
      (footprint "SMD-0402")
      (description "SMD EMI Suppression Ferrite Bead WE-CBF, Z = 600 Ohm")
      (libsource (lib "Altium Content Vault") (part "PAS-IND-INDUCTOR-2"))
    )
    (comp (ref "Q3")
      (value "AO3401A")
      (footprint "AO-SOT-23-3L_V")
      (description "P-Channel MOSFET, 30 V, 4 A, -55 to 150 degC, 3-Pin SOT-23-3L, RoHS, Tape and Reel")
      (fields (field (name "MANUFACTURER") "Alpha and Omega"))
      (libsource (lib "Altium Content Vault") (part "PEMOS-GSD-3"))
    )
    (comp (ref "Q4")
      (value "2N7002-7-F")
      (footprint "FP-SOT23-MFG")
      (description "MOSFET N-CH 60V 115MA SOT23-3")
      (fields (field (name "VOLTAGE") "60V"))
      (libsource (lib "Altium Content Vault") (part "3b9c635fedb024a5347a57b145af9cc"))
    )
    (comp (ref "R52")
      (value "100R")
      (footprint "RESC1005X40X25NL05T05")
      (fields
        (field (name "MANUFACTURER") "Basic Passives")
        (field (name "TOLERANCE") "1%")
        (field (name "PARTNUMBER") "ERJ-2RKF1000X")
      )
      (libsource (lib "Altium Content Vault") (part "RES-2"))
    )
    (comp (ref "R54")
      (value "1K")
      (footprint "RESC1005X40X25NL05T10")
      (description "CRCW04021K00FKEDHP")
      (fields (field (name "MANUFACTURER") "Vishay Dale"))
      (libsource (lib "Altium Content Vault") (part "RES"))
    )
    (comp (ref "R55")
      (value "1K")
      (footprint "RESC1005X40X25NL05T10")
      (description "CRCW04021K00FKEDHP")
      (fields (field (name "MANUFACTURER") "Vishay Dale"))
      (libsource (lib "Altium Content Vault") (part "RES"))
    )
    (comp (ref "R56")
      (value "1K")
      (footprint "RESC1005X40X25NL05T10")
      (description "CRCW04021K00FKEDHP")
      (fields (field (name "MANUFACTURER") "Vishay Dale"))
      (libsource (lib "Altium Content Vault") (part "RES"))
    )
    (comp (ref "R57")
      (value "1K")
      (footprint "RESC1005X40X25NL05T10")
      (description "CRCW04021K00FKEDHP")
      (fields (field (name "MANUFACTURER") "Vishay Dale"))
      (libsource (lib "Altium Content Vault") (part "RES"))
    )
    (comp (ref "R58")
      (value "1K")
      (footprint "RESC1005X40X25NL05T10")
      (description "CRCW04021K00FKEDHP")
      (fields (field (name "MANUFACTURER") "Vishay Dale"))
      (libsource (lib "Altium Content Vault") (part "RES"))
    )
    (comp (ref "R59")
      (value "1K")
      (footprint "RESC1005X40X25NL05T10")
      (description "CRCW04021K00FKEDHP")
      (fields (field (name "MANUFACTURER") "Vishay Dale"))
      (libsource (lib "Altium Content Vault") (part "RES"))
    )
    (comp (ref "R60")
      (value "3.3K")
      (footprint "RESC1005X40X25NL05T10")
      (description "CRCW04023K30FKEDHP")
      (fields (field (name "MANUFACTURER") "Vishay Dale"))
      (libsource (lib "Altium Content Vault") (part "RES"))
    )
    (comp (ref "R61")
      (value "1K")
      (footprint "RESC1005X40X25NL05T10")
      (description "CRCW04021K00FKEDHP")
      (fields (field (name "MANUFACTURER") "Vishay Dale"))
      (libsource (lib "Altium Content Vault") (part "RES"))
    )
    (comp (ref "R62")
      (value "3.3K")
      (footprint "RESC1005X40X25NL05T10")
      (description "CRCW04023K30FKEDHP")
      (fields (field (name "MANUFACTURER") "Vishay Dale"))
      (libsource (lib "Altium Content Vault") (part "RES"))
    )
    (comp (ref "R63")
      (value "1K")
      (footprint "RESC1005X40X25NL05T10")
      (description "CRCW04021K00FKEDHP")
      (fields (field (name "MANUFACTURER") "Vishay Dale"))
      (libsource (lib "Altium Content Vault") (part "RES"))
    )
    (comp (ref "R64")
      (value "1K")
      (footprint "RESC1005X40X25NL05T10")
      (description "CRCW04021K00FKEDHP")
      (fields (field (name "MANUFACTURER") "Vishay Dale"))
      (libsource (lib "Altium Content Vault") (part "RES"))
    )
    (comp (ref "R65")
      (value "1K")
      (footprint "RESC1005X40X25NL05T10")
      (description "CRCW04021K00FKEDHP")
      (fields (field (name "MANUFACTURER") "Vishay Dale"))
      (libsource (lib "Altium Content Vault") (part "RES"))
    )
    (comp (ref "R66")
      (value "2.4K")
      (footprint "RESC1005X40X25NL05T05")
      (description "CRCW04022K40FKED")
      (fields (field (name "MANUFACTURER") "Vishay Dale"))
      (libsource (lib "Altium Content Vault") (part "RES"))
    )
    (comp (ref "R68")
      (value "0R")
      (footprint "RESC1005X40X25NL05T10")
      (description "CRCW04020000Z0EDHP")
      (fields (field (name "MANUFACTURER") "Vishay Dale"))
      (libsource (lib "Altium Content Vault") (part "RES"))
    )
    (comp (ref "R69")
      (value "0R")
      (footprint "RESC1005X40X25NL05T10")
      (description "CRCW04020000Z0EDHP")
      (fields (field (name "MANUFACTURER") "Vishay Dale"))
      (libsource (lib "Altium Content Vault") (part "RES"))
    )
    (comp (ref "R70")
      (value "0R")
      (footprint "RESC1005X40X25NL05T10")
      (description "CRCW04020000Z0EDHP")
      (fields (field (name "MANUFACTURER") "Vishay Dale"))
      (libsource (lib "Altium Content Vault") (part "RES"))
    )
    (comp (ref "R71")
      (value "0R")
      (footprint "RESC1005X40X25NL05T10")
      (description "CRCW04020000Z0EDHP")
      (fields (field (name "MANUFACTURER") "Vishay Dale"))
      (libsource (lib "Altium Content Vault") (part "RES"))
    )
    (comp (ref "SW6")
      (value "B3S-1000P")
      (footprint "FP-B3S-1000P-MFG")
      (description "SWITCH TACTILE SPST-NO 0.05A 24V")
      (libsource (lib "Altium Content Vault") (part "b8895f3f4cefb76e1819d2863dba89b"))
    )
    (comp (ref "SW7")
      (value "B3S-1000P")
      (footprint "FP-B3S-1000P-MFG")
      (description "SWITCH TACTILE SPST-NO 0.05A 24V")
      (libsource (lib "Altium Content Vault") (part "b8895f3f4cefb76e1819d2863dba89b"))
    )
    (comp (ref "SW8")
      (value "A6S-3101-H")
      (footprint "FP-A6S-3101-H-MFG")
      (description "SWITCH SLIDE DIP SPST 25MA 24V")
      (libsource (lib "Altium Content Vault") (part "3494dd441064fb229d3d9931c8c67f4"))
    )
    (comp (ref "U14")
      (value "XC7A35T-1FGG484C")
      (footprint "FGG484")
      (description "Artix-7 FPGA, 250 User I/Os, 4 GTP, 484-Ball BGA, Speed Grade 1, Commercial Grade, Pb-Free")
      (fields (field (name "MANUFACTURER") "Xilinx"))
      (libsource (lib "") (part "XLNX-XC7A35T-FGG484_6"))
    )
    (comp (ref "U15")
      (value "TC1047AVNBTR")
      (footprint "SOT-23-NB3_L")
      (description "Precision Temperature-to-Voltage Converter, 3-Pin SOT-23, Extended Temperature, Tape and Reel")
      (libsource (lib "Altium Content Vault") (part "CON-TVC-TC1046-3"))
    )
    (comp (ref "U16")
      (value "NX33D5001Q")
      (footprint "SOTFL125P185X90-6N")
      (description "Xtal Osc Xo 135.0000MHZ Lvds SMD")
      (libsource (lib "Main Workspace") (part "NX33D5001Q"))
    )
    (comp (ref "U17")
      (value "REF3012AIDBZT")
      (footprint "DBZ0003A_L")
      (fields (field (name "MANUFACTURER") "Texas Instruments"))
      (libsource (lib "Altium Content Vault") (part "TI-REF3012DBZ3"))
    )
    (comp (ref "U18")
      (value "IS25LP128F-JBLE")
      (footprint "SOIC127P790X216-8N")
      (description "Flash, Multi I/O SPI, QPI, DTR, 2.3-3.6V, -40 to 125°C, 8-pin SOIC 208mil, RoHS")
      (libsource (lib "Main Workspace") (part "IS25LP128F-JBLE"))
    )
    (comp (ref "X2")
      (value "O53100000153033")
      (footprint "DFN254P500X120-4N")
      (description "Single Ended CMOS Oscillator 3.3V 100Mhz")
      (libsource (lib "Main Workspace") (part "O53100000153033"))
    )
  )
  (nets
    (net (code "1") (name "+1V0") (class "Default")
      (node (ref "C151") (pin "2") (pinfunction "2_2") (pintype "passive"))
      (node (ref "C152") (pin "2") (pinfunction "2_2") (pintype "passive"))
      (node (ref "C153") (pin "2") (pinfunction "2_2") (pintype "passive"))
      (node (ref "C154") (pin "2") (pinfunction "2_2") (pintype "passive"))
      (node (ref "C155") (pin "2") (pinfunction "2_2") (pintype "passive"))
      (node (ref "C156") (pin "2") (pinfunction "2_2") (pintype "passive"))
      (node (ref "C157") (pin "2") (pinfunction "2_2") (pintype "passive"))
      (node (ref "C201") (pin "2") (pinfunction "2_2") (pintype "passive"))
      (node (ref "C202") (pin "2") (pinfunction "2_2") (pintype "passive"))
      (node (ref "C203") (pin "2") (pinfunction "2_2") (pintype "passive"))
      (node (ref "C204") (pin "2") (pinfunction "2_2") (pintype "passive"))
      (node (ref "C205") (pin "2") (pinfunction "2_2") (pintype "passive"))
      (node (ref "C206") (pin "2") (pinfunction "2_2") (pintype "passive"))
      (node (ref "C207") (pin "2") (pinfunction "2_2") (pintype "passive"))
      (node (ref "C208") (pin "2") (pinfunction "2_2") (pintype "passive"))
      (node (ref "C209") (pin "2") (pinfunction "2_2") (pintype "passive"))
      (node (ref "C216") (pin "2") (pinfunction "2_2") (pintype "passive"))
      (node (ref "C217") (pin "2") (pinfunction "2_2") (pintype "passive"))
      (node (ref "C218") (pin "2") (pinfunction "2_2") (pintype "passive"))
      (node (ref "C219") (pin "2") (pinfunction "2_2") (pintype "passive"))
      (node (ref "C220") (pin "2") (pinfunction "2_2") (pintype "passive"))
      (node (ref "C221") (pin "2") (pinfunction "2_2") (pintype "passive"))
      (node (ref "C222") (pin "2") (pinfunction "2_2") (pintype "passive"))
      (node (ref "C223") (pin "2") (pinfunction "2_2") (pintype "passive"))
      (node (ref "C224") (pin "2") (pinfunction "2_2") (pintype "passive"))
      (node (ref "C225") (pin "2") (pinfunction "2_2") (pintype "passive"))
      (node (ref "C226") (pin "2") (pinfunction "2_2") (pintype "passive"))
      (node (ref "C227") (pin "2") (pinfunction "2_2") (pintype "passive"))
      (node (ref "C228") (pin "2") (pinfunction "2_2") (pintype "passive"))
      (node (ref "U14") (pin "D10") (pinfunction "MGTAVCC_D10") (pintype "power_in"))
      (node (ref "U14") (pin "D6") (pinfunction "MGTAVCC_D6") (pintype "power_in"))
      (node (ref "U14") (pin "E8") (pinfunction "MGTAVCC_E8") (pintype "power_in"))
      (node (ref "U14") (pin "F7") (pinfunction "MGTAVCC_F7") (pintype "power_in"))
      (node (ref "U14") (pin "F9") (pinfunction "MGTAVCC_F9") (pintype "power_in"))
      (node (ref "U14") (pin "H10") (pinfunction "VCCINT_H10") (pintype "power_in"))
      (node (ref "U14") (pin "H8") (pinfunction "VCCINT_H8") (pintype "power_in"))
      (node (ref "U14") (pin "J11") (pinfunction "VCCBRAM_J11") (pintype "power_in"))
      (node (ref "U14") (pin "J7") (pinfunction "VCCINT_J7") (pintype "power_in"))
      (node (ref "U14") (pin "J9") (pinfunction "VCCINT_J9") (pintype "power_in"))
      (node (ref "U14") (pin "K8") (pinfunction "VCCINT_K8") (pintype "power_in"))
      (node (ref "U14") (pin "L11") (pinfunction "VCCBRAM_L11") (pintype "power_in"))
      (node (ref "U14") (pin "L7") (pinfunction "VCCINT_L7") (pintype "power_in"))
      (node (ref "U14") (pin "M8") (pinfunction "VCCINT_M8") (pintype "power_in"))
      (node (ref "U14") (pin "N11") (pinfunction "VCCBRAM_N11") (pintype "power_in"))
      (node (ref "U14") (pin "N7") (pinfunction "VCCINT_N7") (pintype "power_in"))
      (node (ref "U14") (pin "P10") (pinfunction "VCCINT_P10") (pintype "power_in"))
      (node (ref "U14") (pin "P8") (pinfunction "VCCINT_P8") (pintype "power_in"))
      (node (ref "U14") (pin "R7") (pinfunction "VCCINT_R7") (pintype "power_in"))
      (node (ref "U14") (pin "R9") (pinfunction "VCCINT_R9") (pintype "power_in"))
      (node (ref "U14") (pin "T10") (pinfunction "VCCINT_T10") (pintype "power_in"))
      (node (ref "U14") (pin "T8") (pinfunction "VCCINT_T8") (pintype "power_in"))
    )
    (net (code "2") (name "+1V2") (class "Default")
      (node (ref "C134") (pin "2") (pinfunction "2_2") (pintype "passive"))
      (node (ref "C143") (pin "2") (pinfunction "2_2") (pintype "passive"))
      (node (ref "C144") (pin "2") (pinfunction "2_2") (pintype "passive"))
      (node (ref "C145") (pin "2") (pinfunction "2_2") (pintype "passive"))
      (node (ref "C146") (pin "2") (pinfunction "2_2") (pintype "passive"))
      (node (ref "C147") (pin "2") (pinfunction "2_2") (pintype "passive"))
      (node (ref "C148") (pin "2") (pinfunction "2_2") (pintype "passive"))
      (node (ref "C149") (pin "2") (pinfunction "2_2") (pintype "passive"))
      (node (ref "C150") (pin "2") (pinfunction "2_2") (pintype "passive"))
      (node (ref "R52") (pin "1") (pinfunction "1_1") (pintype "passive"))
      (node (ref "U14") (pin "B11") (pinfunction "MGTAVTT_B11") (pintype "power_in"))
      (node (ref "U14") (pin "B5") (pinfunction "MGTAVTT_B5") (pintype "power_in"))
      (node (ref "U14") (pin "B7") (pinfunction "MGTAVTT_B7") (pintype "power_in"))
      (node (ref "U14") (pin "B9") (pinfunction "MGTAVTT_B9") (pintype "power_in"))
      (node (ref "U14") (pin "C4") (pinfunction "MGTAVTT_C4") (pintype "power_in"))
      (node (ref "U14") (pin "C8") (pinfunction "MGTAVTT_C8") (pintype "power_in"))
    )
    (net (code "3") (name "+1V8") (class "Default")
      (node (ref "C184") (pin "2") (pinfunction "2_2") (pintype "passive"))
      (node (ref "C185") (pin "2") (pinfunction "2_2") (pintype "passive"))
      (node (ref "C186") (pin "2") (pinfunction "2_2") (pintype "passive"))
      (node (ref "C187") (pin "2") (pinfunction "2_2") (pintype "passive"))
      (node (ref "C188") (pin "2") (pinfunction "2_2") (pintype "passive"))
      (node (ref "C189") (pin "2") (pinfunction "2_2") (pintype "passive"))
      (node (ref "C198") (pin "2") (pinfunction "2_2") (pintype "passive"))
      (node (ref "C199") (pin "2") (pinfunction "2_2") (pintype "passive"))
      (node (ref "C210") (pin "2") (pinfunction "2_2") (pintype "passive"))
      (node (ref "C211") (pin "2") (pinfunction "2_2") (pintype "passive"))
      (node (ref "C212") (pin "2") (pinfunction "2_2") (pintype "passive"))
      (node (ref "C213") (pin "2") (pinfunction "2_2") (pintype "passive"))
      (node (ref "C214") (pin "2") (pinfunction "2_2") (pintype "passive"))
      (node (ref "C215") (pin "2") (pinfunction "2_2") (pintype "passive"))
      (node (ref "U14") (pin "C1") (pinfunction "VCCO_35_C1") (pintype "power_in"))
      (node (ref "U14") (pin "E12") (pinfunction "VCCBATT_0_E12") (pintype "power_in"))
      (node (ref "U14") (pin "F2") (pinfunction "VCCO_35_F2") (pintype "power_in"))
      (node (ref "U14") (pin "H12") (pinfunction "VCCAUX_H12") (pintype "power_in"))
      (node (ref "U14") (pin "H6") (pinfunction "VCCO_35_H6") (pintype "power_in"))
      (node (ref "U14") (pin "J3") (pinfunction "VCCO_35_J3") (pintype "power_in"))
      (node (ref "U14") (pin "K10") (pinfunction "VCCADC_0_K10") (pintype "power_in"))
      (node (ref "U14") (pin "K12") (pinfunction "VCCAUX_K12") (pintype "power_in"))
      (node (ref "U14") (pin "M12") (pinfunction "VCCAUX_M12") (pintype "power_in"))
      (node (ref "U14") (pin "M4") (pinfunction "VCCO_35_M4") (pintype "power_in"))
      (node (ref "U14") (pin "N1") (pinfunction "VCCO_35_N1") (pintype "power_in"))
      (node (ref "U14") (pin "P12") (pinfunction "VCCAUX_P12") (pintype "power_in"))
      (node (ref "U14") (pin "R11") (pinfunction "VCCAUX_R11") (pintype "power_in"))
    )
    (net (code "4") (name "+3V3") (class "Default")
      (node (ref "C137") (pin "2") (pinfunction "2_2") (pintype "passive"))
      (node (ref "C140") (pin "2") (pinfunction "2_2") (pintype "passive"))
      (node (ref "C141") (pin "2") (pinfunction "2_2") (pintype "passive"))
      (node (ref "C158") (pin "2") (pinfunction "2_2") (pintype "passive"))
      (node (ref "C159") (pin "2") (pinfunction "2_2") (pintype "passive"))
      (node (ref "C161") (pin "2") (pinfunction "2_2") (pintype "passive"))
      (node (ref "C162") (pin "2") (pinfunction "2_2") (pintype "passive"))
      (node (ref "C163") (pin "2") (pinfunction "2_2") (pintype "passive"))
      (node (ref "C164") (pin "2") (pinfunction "2_2") (pintype "passive"))
      (node (ref "C165") (pin "2") (pinfunction "2_2") (pintype "passive"))
      (node (ref "C166") (pin "2") (pinfunction "2_2") (pintype "passive"))
      (node (ref "C167") (pin "2") (pinfunction "2_2") (pintype "passive"))
      (node (ref "C168") (pin "2") (pinfunction "2_2") (pintype "passive"))
      (node (ref "C169") (pin "2") (pinfunction "2_2") (pintype "passive"))
      (node (ref "C170") (pin "2") (pinfunction "2_2") (pintype "passive"))
      (node (ref "C171") (pin "2") (pinfunction "2_2") (pintype "passive"))
      (node (ref "C172") (pin "2") (pinfunction "2_2") (pintype "passive"))
      (node (ref "C173") (pin "2") (pinfunction "2_2") (pintype "passive"))
      (node (ref "C174") (pin "2") (pinfunction "2_2") (pintype "passive"))
      (node (ref "C175") (pin "2") (pinfunction "2_2") (pintype "passive"))
      (node (ref "C176") (pin "2") (pinfunction "2_2") (pintype "passive"))
      (node (ref "C177") (pin "2") (pinfunction "2_2") (pintype "passive"))
      (node (ref "C178") (pin "2") (pinfunction "2_2") (pintype "passive"))
      (node (ref "C179") (pin "2") (pinfunction "2_2") (pintype "passive"))
      (node (ref "C180") (pin "2") (pinfunction "2_2") (pintype "passive"))
      (node (ref "C181") (pin "2") (pinfunction "2_2") (pintype "passive"))
      (node (ref "C182") (pin "2") (pinfunction "2_2") (pintype "passive"))
      (node (ref "C183") (pin "2") (pinfunction "2_2") (pintype "passive"))
      (node (ref "C190") (pin "2") (pinfunction "2_2") (pintype "passive"))
      (node (ref "C191") (pin "2") (pinfunction "2_2") (pintype "passive"))
      (node (ref "C192") (pin "2") (pinfunction "2_2") (pintype "passive"))
      (node (ref "C193") (pin "2") (pinfunction "2_2") (pintype "passive"))
      (node (ref "C194") (pin "2") (pinfunction "2_2") (pintype "passive"))
      (node (ref "C195") (pin "2") (pinfunction "2_2") (pintype "passive"))
      (node (ref "C196") (pin "2") (pinfunction "2_2") (pintype "passive"))
      (node (ref "C200") (pin "2") (pinfunction "2_2") (pintype "passive"))
      (node (ref "C342") (pin "2") (pinfunction "2_2") (pintype "passive"))
      (node (ref "C343") (pin "2") (pinfunction "2_2") (pintype "passive"))
      (node (ref "Q3") (pin "2") (pinfunction "SOURCE_2") (pintype "passive"))
      (node (ref "R54") (pin "2") (pinfunction "2_2") (pintype "passive"))
      (node (ref "R55") (pin "2") (pinfunction "2_2") (pintype "passive"))
      (node (ref "R56") (pin "2") (pinfunction "2_2") (pintype "passive"))
      (node (ref "R57") (pin "2") (pinfunction "2_2") (pintype "passive"))
      (node (ref "R58") (pin "2") (pinfunction "2_2") (pintype "passive"))
      (node (ref "R59") (pin "2") (pinfunction "2_2") (pintype "passive"))
      (node (ref "R60") (pin "2") (pinfunction "2_2") (pintype "passive"))
      (node (ref "R62") (pin "2") (pinfunction "2_2") (pintype "passive"))
      (node (ref "R65") (pin "2") (pinfunction "2_2") (pintype "passive"))
      (node (ref "R66") (pin "2") (pinfunction "2_2") (pintype "passive"))
      (node (ref "U14") (pin "A17") (pinfunction "VCCO_16_A17") (pintype "power_in"))
      (node (ref "U14") (pin "AA17") (pinfunction "VCCO_13_AA17") (pintype "power_in"))
      (node (ref "U14") (pin "AA7") (pinfunction "VCCO_34_AA7") (pintype "power_in"))
      (node (ref "U14") (pin "AB14") (pinfunction "VCCO_13_AB14") (pintype "power_in"))
      (node (ref "U14") (pin "AB4") (pinfunction "VCCO_34_AB4") (pintype "power_in"))
      (node (ref "U14") (pin "B14") (pinfunction "VCCO_16_B14") (pintype "power_in"))
      (node (ref "U14") (pin "C21") (pinfunction "VCCO_16_C21") (pintype "power_in"))
      (node (ref "U14") (pin "D18") (pinfunction "VCCO_16_D18") (pintype "power_in"))
      (node (ref "U14") (pin "E15") (pinfunction "VCCO_16_E15") (pintype "power_in"))
      (node (ref "U14") (pin "F12") (pinfunction "VCCO_0_F12") (pintype "power_in"))
      (node (ref "U14") (pin "F22") (pinfunction "VCCO_16_F22") (pintype "power_in"))
      (node (ref "U14") (pin "G19") (pinfunction "VCCO_15_G19") (pintype "power_in"))
      (node (ref "U14") (pin "H16") (pinfunction "VCCO_15_H16") (pintype "power_in"))
      (node (ref "U14") (pin "J13") (pinfunction "VCCO_15_J13") (pintype "power_in"))
      (node (ref "U14") (pin "K20") (pinfunction "VCCO_15_K20") (pintype "power_in"))
      (node (ref "U14") (pin "L17") (pinfunction "VCCO_15_L17") (pintype "power_in"))
      (node (ref "U14") (pin "M14") (pinfunction "VCCO_14_M14") (pintype "power_in"))
      (node (ref "U14") (pin "N21") (pinfunction "VCCO_15_N21") (pintype "power_in"))
      (node (ref "U14") (pin "P18") (pinfunction "VCCO_14_P18") (pintype "power_in"))
      (node (ref "U14") (pin "R15") (pinfunction "VCCO_14_R15") (pintype "power_in"))
      (node (ref "U14") (pin "R5") (pinfunction "VCCO_34_R5") (pintype "power_in"))
      (node (ref "U14") (pin "T12") (pinfunction "VCCO_0_T12") (pintype "power_in"))
      (node (ref "U14") (pin "T2") (pinfunction "VCCO_34_T2") (pintype "power_in"))
      (node (ref "U14") (pin "T22") (pinfunction "VCCO_14_T22") (pintype "power_in"))
      (node (ref "U14") (pin "U19") (pinfunction "VCCO_14_U19") (pintype "power_in"))
      (node (ref "U14") (pin "V16") (pinfunction "VCCO_13_V16") (pintype "power_in"))
      (node (ref "U14") (pin "V6") (pinfunction "VCCO_34_V6") (pintype "power_in"))
      (node (ref "U14") (pin "W13") (pinfunction "VCCO_13_W13") (pintype "power_in"))
      (node (ref "U14") (pin "W3") (pinfunction "VCCO_34_W3") (pintype "power_in"))
      (node (ref "U14") (pin "Y10") (pinfunction "VCCO_13_Y10") (pintype "power_in"))
      (node (ref "U14") (pin "Y20") (pinfunction "VCCO_14_Y20") (pintype "power_in"))
      (node (ref "U15") (pin "1") (pinfunction "VDD_1") (pintype "power_in"))
      (node (ref "U16") (pin "1") (pinfunction "OE_1") (pintype "passive"))
      (node (ref "U16") (pin "6") (pinfunction "VCC_6") (pintype "passive"))
      (node (ref "U17") (pin "1") (pinfunction "IN_1") (pintype "power_in"))
      (node (ref "U18") (pin "3") (pinfunction "WP#_3") (pintype "passive"))
      (node (ref "U18") (pin "7") (pinfunction "HOLD/RST_7") (pintype "passive"))
      (node (ref "U18") (pin "8") (pinfunction "VCC_8") (pintype "passive"))
      (node (ref "X2") (pin "1") (pinfunction "EN_1") (pintype "passive"))
      (node (ref "X2") (pin "4") (pinfunction "VDD_4") (pintype "passive"))
    )
    (net (code "5") (name "/FPGA0_ADC_IN_N") (class "Default")
      (node (ref "R69") (pin "1") (pinfunction "1_1") (pintype "passive"))
      (node (ref "R71") (pin "1") (pinfunction "1_1") (pintype "passive"))
      (node (ref "U14") (pin "M9") (pinfunction "VN_0_M9") (pintype "input"))
    )
    (net (code "6") (name "/FPGA0_ADC_IN_P") (class "Default")
      (node (ref "R68") (pin "1") (pinfunction "1_1") (pintype "passive"))
      (node (ref "R69") (pin "2") (pinfunction "2_2") (pintype "passive"))
      (node (ref "U14") (pin "L10") (pinfunction "VP_0_L10") (pintype "input"))
    )
    (net (code "7") (name "/FPGA0_ADC_IN_R_N") (class "Default")
      (node (ref "J3") (pin "2") (pinfunction "2_2") (pintype "passive"))
      (node (ref "J3") (pin "3") (pinfunction "3_3") (pintype "passive"))
      (node (ref "J3") (pin "4") (pinfunction "4_4") (pintype "passive"))
      (node (ref "J3") (pin "5") (pinfunction "5_5") (pintype "passive"))
      (node (ref "R70") (pin "1") (pinfunction "1_1") (pintype "passive"))
      (node (ref "R71") (pin "2") (pinfunction "2_2") (pintype "passive"))
    )
    (net (code "8") (name "/FPGA0_ADC_IN_R_P") (class "Default")
      (node (ref "J3") (pin "1") (pinfunction "1_1") (pintype "passive"))
      (node (ref "R68") (pin "2") (pinfunction "2_2") (pintype "passive"))
      (node (ref "R70") (pin "2") (pinfunction "2_2") (pintype "passive"))
    )
    (net (code "9") (name "/FPGA0_ADC_VREF_N") (class "Default")
      (node (ref "C197") (pin "1") (pinfunction "1_1") (pintype "passive"))
      (node (ref "L6") (pin "2") (pinfunction "2_2") (pintype "passive"))
      (node (ref "U14") (pin "L9") (pinfunction "VREFN_0_L9") (pintype "input"))
    )
    (net (code "10") (name "/FPGA0_ADC_VREF_P") (class "Default")
      (node (ref "C197") (pin "2") (pinfunction "2_2") (pintype "passive"))
      (node (ref "U14") (pin "M10") (pinfunction "VREFP_0_M10") (pintype "input"))
      (node (ref "U17") (pin "2") (pinfunction "OUT_2") (pintype "power_in"))
    )
    (net (code "11") (name "/FPGA0_CFGBVS") (class "Default")
      (node (ref "R57") (pin "1") (pinfunction "1_1") (pintype "passive"))
      (node (ref "U14") (pin "U8") (pinfunction "CFGBVS_0_U8") (pintype "input"))
    )
    (net (code "12") (name "/FPGA0_CLK_N") (class "Default")
      (node (ref "U14") (pin "E10") (pinfunction "MGTREFCLK1N_216_E10") (pintype "input"))
    )
    (net (code "13") (name "/FPGA0_CLK_P") (class "Default")
      (node (ref "U14") (pin "F10") (pinfunction "MGTREFCLK1P_216_F10") (pintype "input"))
    )
    (net (code "14") (name "/FPGA0_DONE") (class "Default")
      (node (ref "Q4") (pin "1") (pinfunction "G_1") (pintype "passive"))
      (node (ref "U14") (pin "G11") (pinfunction "DONE_0_G11") (pintype "bidirectional"))
    )
    (net (code "15") (name "/FPGA0_FLASH_CLK") (class "Default")
      (node (ref "U14") (pin "L12") (pinfunction "CCLK_0_L12") (pintype "bidirectional"))
      (node (ref "U18") (pin "6") (pinfunction "SCK_6") (pintype "passive"))
    )
    (net (code "16") (name "/FPGA0_FLASH_DIN") (class "Default")
      (node (ref "U14") (pin "R22") (pinfunction "IO_L1N_T0_D01_DIN_14_R22") (pintype "bidirectional"))
      (node (ref "U18") (pin "2") (pinfunction "SO_2") (pintype "passive"))
    )
    (net (code "17") (name "/FPGA0_FLASH_DOUT") (class "Default")
      (node (ref "U14") (pin "P22") (pinfunction "IO_L1P_T0_D00_MOSI_14_P22") (pintype "bidirectional"))
      (node (ref "U18") (pin "5") (pinfunction "SI_5") (pintype "passive"))
    )
    (net (code "18") (name "/FPGA0_FLASH_FCS_B") (class "Default")
      (node (ref "R66") (pin "1") (pinfunction "1_1") (pintype "passive"))
      (node (ref "U14") (pin "T19") (pinfunction "IO_L6P_T0_FCS_B_14_T19") (pintype "bidirectional"))
      (node (ref "U18") (pin "1") (pinfunction "CE#_1") (pintype "passive"))
    )
    (net (code "19") (name "/FPGA0_GTP_CLK_C_N") (class "Default")
      (node (ref "C139") (pin "2") (pinfunction "2_2") (pintype "passive"))
      (node (ref "U16") (pin "5") (pinfunction "OUT_N_5") (pintype "passive"))
    )
    (net (code "20") (name "/FPGA0_GTP_CLK_C_P") (class "Default")
      (node (ref "C138") (pin "2") (pinfunction "2_2") (pintype "passive"))
      (node (ref "U16") (pin "4") (pinfunction "OUT_P_4") (pintype "passive"))
    )
    (net (code "21") (name "/FPGA0_GTP_CLK_N") (class "Default")
      (node (ref "C139") (pin "1") (pinfunction "1_1") (pintype "passive"))
      (node (ref "U14") (pin "E6") (pinfunction "MGTREFCLK0N_216_E6") (pintype "input"))
    )
    (net (code "22") (name "/FPGA0_GTP_CLK_P") (class "Default")
      (node (ref "C138") (pin "1") (pinfunction "1_1") (pintype "passive"))
      (node (ref "U14") (pin "F6") (pinfunction "MGTREFCLK0P_216_F6") (pintype "input"))
    )
    (net (code "23") (name "/FPGA0_INITB") (class "Default")
      (node (ref "Q3") (pin "1") (pinfunction "GATE_1") (pintype "passive"))
      (node (ref "R58") (pin "1") (pinfunction "1_1") (pintype "passive"))
      (node (ref "U14") (pin "U12") (pinfunction "INIT_B_0_U12") (pintype "bidirectional"))
    )
    (net (code "24") (name "/FPGA0_LED0") (class "Default")
      (node (ref "U14") (pin "N13") (pinfunction "IO_L23P_T3_A03_D19_14_N13") (pintype "bidirectional"))
    )
    (net (code "25") (name "/FPGA0_LED1") (class "Default")
      (node (ref "U14") (pin "N14") (pinfunction "IO_L23N_T3_A02_D18_14_N14") (pintype "bidirectional"))
    )
    (net (code "26") (name "/FPGA0_LED2") (class "Default")
      (node (ref "U14") (pin "P14") (pinfunction "IO_L19P_T3_A10_D26_14_P14") (pintype "bidirectional"))
    )
    (net (code "27") (name "/FPGA0_LED3") (class "Default")
      (node (ref "U14") (pin "N15") (pinfunction "IO_25_14_N15") (pintype "bidirectional"))
    )
    (net (code "28") (name "/FPGA0_LED4") (class "Default")
      (node (ref "U14") (pin "R16") (pinfunction "IO_L22N_T3_A04_D20_14_R16") (pintype "bidirectional"))
    )
    (net (code "29") (name "/FPGA0_LED5") (class "Default")
      (node (ref "U14") (pin "P17") (pinfunction "IO_L21N_T3_DQS_A06_D22_14_P17") (pintype "bidirectional"))
    )
    (net (code "30") (name "/FPGA0_LED6") (class "Default")
      (node (ref "U14") (pin "P15") (pinfunction "IO_L22P_T3_A05_D21_14_P15") (pintype "bidirectional"))
    )
    (net (code "31") (name "/FPGA0_LED7") (class "Default")
      (node (ref "U14") (pin "P16") (pinfunction "IO_L24P_T3_A01_D17_14_P16") (pintype "bidirectional"))
    )
    (net (code "33") (name "/FPGA0_M0") (class "Default")
      (node (ref "R54") (pin "1") (pinfunction "1_1") (pintype "passive"))
      (node (ref "SW8") (pin "1") (pinfunction "1_1") (pintype "passive"))
      (node (ref "U14") (pin "U11") (pinfunction "M0_0_U11") (pintype "input"))
    )
    (net (code "34") (name "/FPGA0_M1") (class "Default")
      (node (ref "R55") (pin "1") (pinfunction "1_1") (pintype "passive"))
      (node (ref "SW8") (pin "2") (pinfunction "2_2") (pintype "passive"))
      (node (ref "U14") (pin "U10") (pinfunction "M1_0_U10") (pintype "input"))
    )
    (net (code "35") (name "/FPGA0_M2") (class "Default")
      (node (ref "R56") (pin "1") (pinfunction "1_1") (pintype "passive"))
      (node (ref "SW8") (pin "3") (pinfunction "3_3") (pintype "passive"))
      (node (ref "U14") (pin "U9") (pinfunction "M2_0_U9") (pintype "input"))
    )
    (net (code "36") (name "/FPGA0_PROGB") (class "Default")
      (node (ref "R61") (pin "1") (pinfunction "1_1") (pintype "passive"))
      (node (ref "U14") (pin "N12") (pinfunction "PROGRAM_B_0_N12") (pintype "input"))
    )
    (net (code "37") (name "/FPGA0_PUDC_B") (class "Default")
      (node (ref "R59") (pin "1") (pinfunction "1_1") (pintype "passive"))
      (node (ref "U14") (pin "U22") (pinfunction "IO_L3P_T0_DQS_PUDC_B_14_U22") (pintype "bidirectional"))
    )
    (net (code "38") (name "/FPGA0_RX0_N") (class "Default")
      (node (ref "U14") (pin "A8") (pinfunction "MGTPRXN0_216_A8") (pintype "input"))
    )
    (net (code "39") (name "/FPGA0_RX0_P") (class "Default")
      (node (ref "U14") (pin "B8") (pinfunction "MGTPRXP0_216_B8") (pintype "input"))
    )
    (net (code "40") (name "/FPGA0_RX1_N") (class "Default")
      (node (ref "U14") (pin "C11") (pinfunction "MGTPRXN1_216_C11") (pintype "input"))
    )
    (net (code "41") (name "/FPGA0_RX1_P") (class "Default")
      (node (ref "U14") (pin "D11") (pinfunction "MGTPRXP1_216_D11") (pintype "input"))
    )
    (net (code "42") (name "/FPGA0_RX2_N") (class "Default")
      (node (ref "U14") (pin "A10") (pinfunction "MGTPRXN2_216_A10") (pintype "input"))
    )
    (net (code "43") (name "/FPGA0_RX2_P") (class "Default")
      (node (ref "U14") (pin "B10") (pinfunction "MGTPRXP2_216_B10") (pintype "input"))
    )
    (net (code "44") (name "/FPGA0_RX3_N") (class "Default")
      (node (ref "U14") (pin "C9") (pinfunction "MGTPRXN3_216_C9") (pintype "input"))
    )
    (net (code "45") (name "/FPGA0_RX3_P") (class "Default")
      (node (ref "U14") (pin "D9") (pinfunction "MGTPRXP3_216_D9") (pintype "input"))
    )
    (net (code "46") (name "/FPGA0_SYS_CLK_P") (class "Default")
      (node (ref "C136") (pin "2") (pinfunction "2_2") (pintype "passive"))
      (node (ref "U14") (pin "Y18") (pinfunction "IO_L13P_T2_MRCC_14_Y18") (pintype "input"))
      (node (ref "X2") (pin "3") (pinfunction "OUT_3") (pintype "passive"))
    )
    (net (code "47") (name "/FPGA0_SYS_RST") (class "Default")
      (node (ref "R63") (pin "1") (pinfunction "1_1") (pintype "passive"))
      (node (ref "U14") (pin "V18") (pinfunction "IO_L14P_T2_SRCC_14_V18") (pintype "bidirectional"))
    )
    (net (code "48") (name "/FPGA0_TX0_N") (class "Default")
      (node (ref "U14") (pin "A4") (pinfunction "MGTPTXN0_216_A4") (pintype "output"))
    )
    (net (code "49") (name "/FPGA0_TX0_P") (class "Default")
      (node (ref "U14") (pin "B4") (pinfunction "MGTPTXP0_216_B4") (pintype "output"))
    )
    (net (code "50") (name "/FPGA0_TX1_N") (class "Default")
      (node (ref "U14") (pin "C5") (pinfunction "MGTPTXN1_216_C5") (pintype "output"))
    )
    (net (code "51") (name "/FPGA0_TX1_P") (class "Default")
      (node (ref "U14") (pin "D5") (pinfunction "MGTPTXP1_216_D5") (pintype "output"))
    )
    (net (code "52") (name "/FPGA0_TX2_N") (class "Default")
      (node (ref "U14") (pin "C7") (pinfunction "MGTPTXN3_216_C7") (pintype "output"))
    )
    (net (code "53") (name "/FPGA0_TX2_P") (class "Default")
      (node (ref "U14") (pin "D7") (pinfunction "MGTPTXP3_216_D7") (pintype "output"))
    )
    (net (code "54") (name "/FPGA0_TX3_N") (class "Default")
      (node (ref "U14") (pin "A6") (pinfunction "MGTPTXN2_216_A6") (pintype "output"))
    )
    (net (code "55") (name "/FPGA0_TX3_P") (class "Default")
      (node (ref "U14") (pin "B6") (pinfunction "MGTPTXP2_216_B6") (pintype "output"))
    )
    (net (code "56") (name "/FPGA_LINK_BUS_IO0") (class "Default")
      (node (ref "U14") (pin "L14") (pinfunction "IO_L22P_T3_A17_15_L14") (pintype "bidirectional"))
    )
    (net (code "57") (name "/FPGA_LINK_BUS_IO1") (class "Default")
      (node (ref "U14") (pin "J15") (pinfunction "IO_L5P_T0_AD9P_15_J15") (pintype "bidirectional"))
    )
    (net (code "58") (name "/FPGA_LINK_BUS_IO2") (class "Default")
      (node (ref "U14") (pin "M13") (pinfunction "IO_L20P_T3_A20_15_M13") (pintype "bidirectional"))
    )
    (net (code "59") (name "/FPGA_LINK_BUS_IO3") (class "Default")
      (node (ref "U14") (pin "M15") (pinfunction "IO_L24P_T3_RS1_15_M15") (pintype "bidirectional"))
    )
    (net (code "60") (name "/FPGA_LINK_BUS_IO4") (class "Default")
      (node (ref "U14") (pin "L15") (pinfunction "IO_L22N_T3_A16_15_L15") (pintype "bidirectional"))
    )
    (net (code "61") (name "/FPGA_LINK_BUS_IO5") (class "Default")
      (node (ref "U14") (pin "L13") (pinfunction "IO_L20N_T3_A19_15_L13") (pintype "bidirectional"))
    )
    (net (code "62") (name "/FPGA_LINK_BUS_IO6") (class "Default")
      (node (ref "U14") (pin "K14") (pinfunction "IO_L19N_T3_A21_VREF_15_K14") (pintype "bidirectional"))
    )
    (net (code "63") (name "/FPGA_LINK_BUS_IO7") (class "Default")
      (node (ref "U14") (pin "K16") (pinfunction "IO_L23N_T3_FWE_B_15_K16") (pintype "bidirectional"))
    )
    (net (code "64") (name "/FPGA_LINK_BUS_IO8") (class "Default")
      (node (ref "U14") (pin "L16") (pinfunction "IO_L23P_T3_FOE_B_15_L16") (pintype "bidirectional"))
    )
    (net (code "65") (name "/FPGA_LINK_BUS_IO9") (class "Default")
      (node (ref "U14") (pin "J14") (pinfunction "IO_L3P_T0_DQS_AD1P_15_J14") (pintype "bidirectional"))
    )
    (net (code "66") (name "/FPGA_LINK_BUS_IO10") (class "Default")
      (node (ref "U14") (pin "H15") (pinfunction "IO_L5N_T0_AD9N_15_H15") (pintype "bidirectional"))
    )
    (net (code "67") (name "/FPGA_LINK_BUS_IO11") (class "Default")
      (node (ref "U14") (pin "J16") (pinfunction "IO_0_15_J16") (pintype "bidirectional"))
    )
    (net (code "68") (name "/FPGA_LINK_BUS_IO12") (class "Default")
      (node (ref "U14") (pin "G17") (pinfunction "IO_L4P_T0_15_G17") (pintype "bidirectional"))
    )
    (net (code "69") (name "/FPGA_LINK_BUS_IO13") (class "Default")
      (node (ref "U14") (pin "H20") (pinfunction "IO_L8P_T1_AD10P_15_H20") (pintype "bidirectional"))
    )
    (net (code "70") (name "/FPGA_LINK_BUS_IO14") (class "Default")
      (node (ref "U14") (pin "K22") (pinfunction "IO_L9N_T1_DQS_AD3N_15_K22") (pintype "bidirectional"))
    )
    (net (code "71") (name "/FPGA_LINK_BUS_IO15") (class "Default")
      (node (ref "U14") (pin "M21") (pinfunction "IO_L10P_T1_AD11P_15_M21") (pintype "bidirectional"))
    )
    (net (code "72") (name "/FPGA_LINK_BUS_IO16") (class "Default")
      (node (ref "U14") (pin "N20") (pinfunction "IO_L18P_T2_A24_15_N20") (pintype "bidirectional"))
    )
    (net (code "73") (name "/FPGA_LINK_BUS_IO17") (class "Default")
      (node (ref "U14") (pin "M18") (pinfunction "IO_L16P_T2_A28_15_M18") (pintype "bidirectional"))
    )
    (net (code "74") (name "/FPGA_LINK_BUS_IO18") (class "Default")
      (node (ref "U14") (pin "L18") (pinfunction "IO_L16N_T2_A27_15_L18") (pintype "bidirectional"))
    )
    (net (code "75") (name "/FPGA_LINK_BUS_IO19") (class "Default")
      (node (ref "U14") (pin "N22") (pinfunction "IO_L15P_T2_DQS_15_N22") (pintype "bidirectional"))
    )
    (net (code "76") (name "/FPGA_LINK_BUS_IO20") (class "Default")
      (node (ref "U14") (pin "L21") (pinfunction "IO_L10N_T1_AD11N_15_L21") (pintype "bidirectional"))
    )
    (net (code "77") (name "/FPGA_LINK_BUS_IO21") (class "Default")
      (node (ref "U14") (pin "J22") (pinfunction "IO_L7P_T1_AD2P_15_J22") (pintype "bidirectional"))
    )
    (net (code "78") (name "/FPGA_LINK_BUS_IO22") (class "Default")
      (node (ref "U14") (pin "J20") (pinfunction "IO_L11P_T1_SRCC_15_J20") (pintype "bidirectional"))
    )
    (net (code "79") (name "/FPGA_LINK_BUS_IO23") (class "Default")
      (node (ref "U14") (pin "G18") (pinfunction "IO_L4N_T0_15_G18") (pintype "bidirectional"))
    )
    (net (code "80") (name "/FPGA_LINK_BUS_IO24") (class "Default")
      (node (ref "U14") (pin "G15") (pinfunction "IO_L2P_T0_AD8P_15_G15") (pintype "bidirectional"))
    )
    (net (code "81") (name "/FPGA_LINK_BUS_IO25") (class "Default")
      (node (ref "U14") (pin "K13") (pinfunction "IO_L19P_T3_A22_15_K13") (pintype "bidirectional"))
    )
    (net (code "82") (name "/FPGA_LINK_BUS_IO26") (class "Default")
      (node (ref "U14") (pin "H13") (pinfunction "IO_L1P_T0_AD0P_15_H13") (pintype "bidirectional"))
    )
    (net (code "83") (name "/FPGA_LINK_BUS_IO27") (class "Default")
      (node (ref "U14") (pin "H14") (pinfunction "IO_L3N_T0_DQS_AD1N_15_H14") (pintype "bidirectional"))
    )
    (net (code "84") (name "/FPGA_LINK_BUS_IO28") (class "Default")
      (node (ref "U14") (pin "G16") (pinfunction "IO_L2N_T0_AD8N_15_G16") (pintype "bidirectional"))
    )
    (net (code "85") (name "/FPGA_LINK_BUS_IO29") (class "Default")
      (node (ref "U14") (pin "H19") (pinfunction "IO_L12N_T1_MRCC_15_H19") (pintype "bidirectional"))
    )
    (net (code "86") (name "/FPGA_LINK_BUS_IO30") (class "Default")
      (node (ref "U14") (pin "H22") (pinfunction "IO_L7N_T1_AD2N_15_H22") (pintype "bidirectional"))
    )
    (net (code "87") (name "/FPGA_LINK_BUS_IO31") (class "Default")
      (node (ref "U14") (pin "K19") (pinfunction "IO_L13N_T2_MRCC_15_K19") (pintype "bidirectional"))
    )
    (net (code "88") (name "/FPGA_LINK_BUS_IO32") (class "Default")
      (node (ref "U14") (pin "L19") (pinfunction "IO_L14P_T2_SRCC_15_L19") (pintype "bidirectional"))
    )
    (net (code "89") (name "/FPGA_LINK_BUS_IO33") (class "Default")
      (node (ref "U14") (pin "N19") (pinfunction "IO_L17N_T2_A25_15_N19") (pintype "bidirectional"))
    )
    (net (code "90") (name "/FPGA_LINK_BUS_IO34") (class "Default")
      (node (ref "U14") (pin "M16") (pinfunction "IO_L24N_T3_RS0_15_M16") (pintype "bidirectional"))
    )
    (net (code "91") (name "/FPGA_LINK_BUS_IO35") (class "Default")
      (node (ref "U14") (pin "M17") (pinfunction "IO_25_15_M17") (pintype "bidirectional"))
    )
    (net (code "92") (name "/FPGA_LINK_BUS_IO36") (class "Default")
      (node (ref "U14") (pin "K17") (pinfunction "IO_L21P_T3_DQS_15_K17") (pintype "bidirectional"))
    )
    (net (code "93") (name "/FPGA_LINK_BUS_IO37") (class "Default")
      (node (ref "U14") (pin "K18") (pinfunction "IO_L13P_T2_MRCC_15_K18") (pintype "bidirectional"))
    )
    (net (code "94") (name "/FPGA_LINK_BUS_IO38") (class "Default")
      (node (ref "U14") (pin "N18") (pinfunction "IO_L17P_T2_A26_15_N18") (pintype "bidirectional"))
    )
    (net (code "95") (name "/FPGA_LINK_BUS_IO39") (class "Default")
      (node (ref "U14") (pin "M20") (pinfunction "IO_L18N_T2_A23_15_M20") (pintype "bidirectional"))
    )
    (net (code "96") (name "/FPGA_LINK_BUS_IO40") (class "Default")
      (node (ref "U14") (pin "M22") (pinfunction "IO_L15N_T2_DQS_ADV_B_15_M22") (pintype "bidirectional"))
    )
    (net (code "97") (name "/FPGA_LINK_BUS_IO41") (class "Default")
      (node (ref "U14") (pin "L20") (pinfunction "IO_L14N_T2_SRCC_15_L20") (pintype "bidirectional"))
    )
    (net (code "98") (name "/FPGA_LINK_BUS_IO42") (class "Default")
      (node (ref "U14") (pin "K21") (pinfunction "IO_L9P_T1_DQS_AD3P_15_K21") (pintype "bidirectional"))
    )
    (net (code "99") (name "/FPGA_LINK_BUS_IO43") (class "Default")
      (node (ref "U14") (pin "J19") (pinfunction "IO_L12P_T1_MRCC_15_J19") (pintype "bidirectional"))
    )
    (net (code "100") (name "/FPGA_LINK_BUS_IO44") (class "Default")
      (node (ref "U14") (pin "J21") (pinfunction "IO_L11N_T1_SRCC_15_J21") (pintype "bidirectional"))
    )
    (net (code "101") (name "/FPGA_LINK_BUS_IO45") (class "Default")
      (node (ref "U14") (pin "J17") (pinfunction "IO_L21N_T3_DQS_A18_15_J17") (pintype "bidirectional"))
    )
    (net (code "102") (name "/FPGA_LINK_BUS_IO46") (class "Default")
      (node (ref "U14") (pin "G20") (pinfunction "IO_L8N_T1_AD10N_15_G20") (pintype "bidirectional"))
    )
    (net (code "103") (name "/FPGA_LINK_BUS_IO47") (class "Default")
      (node (ref "U14") (pin "H18") (pinfunction "IO_L6N_T0_VREF_15_H18") (pintype "bidirectional"))
    )
    (net (code "104") (name "/FPGA_LINK_BUS_IO48") (class "Default")
      (node (ref "U14") (pin "H17") (pinfunction "IO_L6P_T0_15_H17") (pintype "bidirectional"))
    )
    (net (code "105") (name "/FPGA_LINK_BUS_IO49") (class "Default")
      (node (ref "U14") (pin "G13") (pinfunction "IO_L1N_T0_AD0N_15_G13") (pintype "bidirectional"))
    )
    (net (code "106") (name "/FPGA_LINK_BUS_IO50") (class "Default")
      (node (ref "U14") (pin "F13") (pinfunction "IO_L1P_T0_16_F13") (pintype "bidirectional"))
    )
    (net (code "107") (name "/FPGA_LINK_BUS_IO51") (class "Default")
      (node (ref "U14") (pin "E13") (pinfunction "IO_L4P_T0_16_E13") (pintype "bidirectional"))
    )
    (net (code "108") (name "/FPGA_LINK_BUS_IO52") (class "Default")
      (node (ref "U14") (pin "E14") (pinfunction "IO_L4N_T0_16_E14") (pintype "bidirectional"))
    )
    (net (code "109") (name "/FPGA_LINK_BUS_IO53") (class "Default")
      (node (ref "U14") (pin "F18") (pinfunction "IO_L15P_T2_DQS_16_F18") (pintype "bidirectional"))
    )
    (net (code "110") (name "/FPGA_LINK_BUS_IO54") (class "Default")
      (node (ref "U14") (pin "E16") (pinfunction "IO_L5P_T0_16_E16") (pintype "bidirectional"))
    )
    (net (code "111") (name "/FPGA_LINK_BUS_IO55") (class "Default")
      (node (ref "U14") (pin "F15") (pinfunction "IO_0_16_F15") (pintype "bidirectional"))
    )
    (net (code "112") (name "/FPGA_LINK_BUS_IO56") (class "Default")
      (node (ref "U14") (pin "F14") (pinfunction "IO_L1N_T0_16_F14") (pintype "bidirectional"))
    )
    (net (code "113") (name "/FPGA_LINK_BUS_IO57") (class "Default")
      (node (ref "U14") (pin "F16") (pinfunction "IO_L2P_T0_16_F16") (pintype "bidirectional"))
    )
    (net (code "114") (name "/FPGA_LINK_BUS_IO58") (class "Default")
      (node (ref "U14") (pin "E17") (pinfunction "IO_L2N_T0_16_E17") (pintype "bidirectional"))
    )
    (net (code "115") (name "/FPGA_LINK_BUS_IO59") (class "Default")
      (node (ref "U14") (pin "E18") (pinfunction "IO_L15N_T2_DQS_16_E18") (pintype "bidirectional"))
    )
    (net (code "116") (name "/FPGA_LINK_BUS_IO60") (class "Default")
      (node (ref "U14") (pin "G21") (pinfunction "IO_L24P_T3_16_G21") (pintype "bidirectional"))
    )
    (net (code "117") (name "/FPGA_LINK_BUS_IO61") (class "Default")
      (node (ref "U14") (pin "F20") (pinfunction "IO_L18N_T2_16_F20") (pintype "bidirectional"))
    )
    (net (code "118") (name "/FPGA_LINK_BUS_IO62") (class "Default")
      (node (ref "U14") (pin "D19") (pinfunction "IO_L14N_T2_SRCC_16_D19") (pintype "bidirectional"))
    )
    (net (code "119") (name "/FPGA_LINK_BUS_IO63") (class "Default")
      (node (ref "U14") (pin "E21") (pinfunction "IO_L23P_T3_16_E21") (pintype "bidirectional"))
    )
    (net (code "120") (name "/FPGA_LINK_BUS_IO64") (class "Default")
      (node (ref "U14") (pin "F21") (pinfunction "IO_25_16_F21") (pintype "bidirectional"))
    )
    (net (code "121") (name "/FPGA_LINK_BUS_IO65") (class "Default")
      (node (ref "U14") (pin "G22") (pinfunction "IO_L24N_T3_16_G22") (pintype "bidirectional"))
    )
    (net (code "122") (name "/FPGA_LINK_BUS_IO66") (class "Default")
      (node (ref "U14") (pin "F19") (pinfunction "IO_L18P_T2_16_F19") (pintype "bidirectional"))
    )
    (net (code "123") (name "/FPGA_LINK_BUS_IO67") (class "Default")
      (node (ref "U14") (pin "E19") (pinfunction "IO_L14P_T2_SRCC_16_E19") (pintype "bidirectional"))
    )
    (net (code "124") (name "/FPGA_LINK_BUS_IO68") (class "Default")
      (node (ref "U14") (pin "E22") (pinfunction "IO_L22P_T3_16_E22") (pintype "bidirectional"))
    )
    (net (code "125") (name "/FPGA_LINK_BUS_IO69") (class "Default")
      (node (ref "U14") (pin "D22") (pinfunction "IO_L22N_T3_16_D22") (pintype "bidirectional"))
    )
    (net (code "126") (name "/FPGA_LINK_BUS_IO70") (class "Default")
      (node (ref "U14") (pin "C22") (pinfunction "IO_L20P_T3_16_C22") (pintype "bidirectional"))
    )
    (net (code "127") (name "/FPGA_LINK_BUS_IO71") (class "Default")
      (node (ref "U14") (pin "B22") (pinfunction "IO_L20N_T3_16_B22") (pintype "bidirectional"))
    )
    (net (code "128") (name "/FPGA_LINK_BUS_IO72") (class "Default")
      (node (ref "U14") (pin "C19") (pinfunction "IO_L13N_T2_MRCC_16_C19") (pintype "bidirectional"))
    )
    (net (code "129") (name "/FPGA_LINK_BUS_IO73") (class "Default")
      (node (ref "U14") (pin "B20") (pinfunction "IO_L16P_T2_16_B20") (pintype "bidirectional"))
    )
    (net (code "130") (name "/FPGA_LINK_BUS_IO74") (class "Default")
      (node (ref "U14") (pin "C20") (pinfunction "IO_L19N_T3_VREF_16_C20") (pintype "bidirectional"))
    )
    (net (code "131") (name "/FPGA_LINK_BUS_IO75") (class "Default")
      (node (ref "U14") (pin "D20") (pinfunction "IO_L19P_T3_16_D20") (pintype "bidirectional"))
    )
    (net (code "132") (name "/FPGA_LINK_BUS_IO76") (class "Default")
      (node (ref "U14") (pin "D21") (pinfunction "IO_L23N_T3_16_D21") (pintype "bidirectional"))
    )
    (net (code "133") (name "/FPGA_LINK_BUS_IO77") (class "Default")
      (node (ref "U14") (pin "B21") (pinfunction "IO_L21P_T3_DQS_16_B21") (pintype "bidirectional"))
    )
    (net (code "134") (name "/FPGA_LINK_BUS_IO78") (class "Default")
      (node (ref "U14") (pin "A21") (pinfunction "IO_L21N_T3_DQS_16_A21") (pintype "bidirectional"))
    )
    (net (code "135") (name "/FPGA_LINK_BUS_IO79") (class "Default")
      (node (ref "U14") (pin "A20") (pinfunction "IO_L16N_T2_16_A20") (pintype "bidirectional"))
    )
    (net (code "136") (name "/FPGA_LINK_BUS_IO80") (class "Default")
      (node (ref "U14") (pin "A19") (pinfunction "IO_L17N_T2_16_A19") (pintype "bidirectional"))
    )
    (net (code "137") (name "/FPGA_LINK_BUS_IO81") (class "Default")
      (node (ref "U14") (pin "A18") (pinfunction "IO_L17P_T2_16_A18") (pintype "bidirectional"))
    )
    (net (code "138") (name "/FPGA_LINK_BUS_IO82") (class "Default")
      (node (ref "U14") (pin "B16") (pinfunction "IO_L7N_T1_16_B16") (pintype "bidirectional"))
    )
    (net (code "139") (name "/FPGA_LINK_BUS_IO83") (class "Default")
      (node (ref "U14") (pin "D17") (pinfunction "IO_L12P_T1_MRCC_16_D17") (pintype "bidirectional"))
    )
    (net (code "140") (name "/FPGA_LINK_BUS_IO84") (class "Default")
      (node (ref "U14") (pin "C17") (pinfunction "IO_L12N_T1_MRCC_16_C17") (pintype "bidirectional"))
    )
    (net (code "141") (name "/FPGA_LINK_BUS_IO85") (class "Default")
      (node (ref "U14") (pin "B18") (pinfunction "IO_L11N_T1_SRCC_16_B18") (pintype "bidirectional"))
    )
    (net (code "142") (name "/FPGA_LINK_BUS_IO86") (class "Default")
      (node (ref "U14") (pin "C18") (pinfunction "IO_L13P_T2_MRCC_16_C18") (pintype "bidirectional"))
    )
    (net (code "143") (name "/FPGA_LINK_BUS_IO87") (class "Default")
      (node (ref "U14") (pin "B17") (pinfunction "IO_L11P_T1_SRCC_16_B17") (pintype "bidirectional"))
    )
    (net (code "144") (name "/FPGA_LINK_BUS_IO88") (class "Default")
      (node (ref "U14") (pin "A16") (pinfunction "IO_L9N_T1_DQS_16_A16") (pintype "bidirectional"))
    )
    (net (code "145") (name "/FPGA_LINK_BUS_IO89") (class "Default")
      (node (ref "U14") (pin "A15") (pinfunction "IO_L9P_T1_DQS_16_A15") (pintype "bidirectional"))
    )
    (net (code "146") (name "/FPGA_LINK_BUS_IO90") (class "Default")
      (node (ref "U14") (pin "A14") (pinfunction "IO_L10N_T1_16_A14") (pintype "bidirectional"))
    )
    (net (code "147") (name "/FPGA_LINK_BUS_IO91") (class "Default")
      (node (ref "U14") (pin "A13") (pinfunction "IO_L10P_T1_16_A13") (pintype "bidirectional"))
    )
    (net (code "148") (name "/FPGA_LINK_BUS_IO92") (class "Default")
      (node (ref "U14") (pin "C13") (pinfunction "IO_L8P_T1_16_C13") (pintype "bidirectional"))
    )
    (net (code "149") (name "/FPGA_LINK_BUS_IO93") (class "Default")
      (node (ref "U14") (pin "C15") (pinfunction "IO_L3N_T0_DQS_16_C15") (pintype "bidirectional"))
    )
    (net (code "150") (name "/FPGA_LINK_BUS_IO94") (class "Default")
      (node (ref "U14") (pin "B15") (pinfunction "IO_L7P_T1_16_B15") (pintype "bidirectional"))
    )
    (net (code "151") (name "/FPGA_LINK_BUS_IO95") (class "Default")
      (node (ref "U14") (pin "D16") (pinfunction "IO_L5N_T0_16_D16") (pintype "bidirectional"))
    )
    (net (code "152") (name "/FPGA_LINK_BUS_IO96") (class "Default")
      (node (ref "U14") (pin "B13") (pinfunction "IO_L8N_T1_16_B13") (pintype "bidirectional"))
    )
    (net (code "153") (name "/FPGA_LINK_BUS_IO97") (class "Default")
      (node (ref "U14") (pin "C14") (pinfunction "IO_L3P_T0_DQS_16_C14") (pintype "bidirectional"))
    )
    (net (code "154") (name "/FPGA_LINK_BUS_IO98") (class "Default")
      (node (ref "U14") (pin "D15") (pinfunction "IO_L6N_T0_VREF_16_D15") (pintype "bidirectional"))
    )
    (net (code "155") (name "/FPGA_LINK_BUS_IO99") (class "Default")
      (node (ref "U14") (pin "D14") (pinfunction "IO_L6P_T0_16_D14") (pintype "bidirectional"))
    )
    (net (code "157") (name "/HYPERRAM_FPGA0_CLK_N") (class "Default")
      (node (ref "U14") (pin "G4") (pinfunction "IO_L12N_T1_MRCC_35_G4") (pintype "output"))
    )
    (net (code "158") (name "/HYPERRAM_FPGA0_CLK_P") (class "Default")
      (node (ref "U14") (pin "H4") (pinfunction "IO_L12P_T1_MRCC_35_H4") (pintype "output"))
    )
    (net (code "159") (name "/HYPERRAM_FPGA0_CS") (class "Default")
      (node (ref "U14") (pin "B1") (pinfunction "IO_L1P_T0_AD4P_35_B1") (pintype "output"))
    )
    (net (code "160") (name "/HYPERRAM_FPGA0_DQ0") (class "Default")
      (node (ref "U14") (pin "E1") (pinfunction "IO_L3P_T0_DQS_AD5P_35_E1") (pintype "bidirectional"))
    )
    (net (code "161") (name "/HYPERRAM_FPGA0_DQ1") (class "Default")
      (node (ref "U14") (pin "F3") (pinfunction "IO_L6P_T0_35_F3") (pintype "bidirectional"))
    )
    (net (code "162") (name "/HYPERRAM_FPGA0_DQ2") (class "Default")
      (node (ref "U14") (pin "E3") (pinfunction "IO_L6N_T0_VREF_35_E3") (pintype "bidirectional"))
    )
    (net (code "163") (name "/HYPERRAM_FPGA0_DQ3") (class "Default")
      (node (ref "U14") (pin "D1") (pinfunction "IO_L3N_T0_DQS_AD5N_35_D1") (pintype "bidirectional"))
    )
    (net (code "164") (name "/HYPERRAM_FPGA0_DQ4") (class "Default")
      (node (ref "U14") (pin "D2") (pinfunction "IO_L4N_T0_35_D2") (pintype "bidirectional"))
    )
    (net (code "165") (name "/HYPERRAM_FPGA0_DQ5") (class "Default")
      (node (ref "U14") (pin "E2") (pinfunction "IO_L4P_T0_35_E2") (pintype "bidirectional"))
    )
    (net (code "166") (name "/HYPERRAM_FPGA0_DQ6") (class "Default")
      (node (ref "U14") (pin "F1") (pinfunction "IO_L5N_T0_AD13N_35_F1") (pintype "bidirectional"))
    )
    (net (code "167") (name "/HYPERRAM_FPGA0_DQ7") (class "Default")
      (node (ref "U14") (pin "G1") (pinfunction "IO_L5P_T0_AD13P_35_G1") (pintype "bidirectional"))
    )
    (net (code "169") (name "/HYPERRAM_FPGA0_RST") (class "Default")
      (node (ref "U14") (pin "A1") (pinfunction "IO_L1N_T0_AD4N_35_A1") (pintype "output"))
    )
    (net (code "170") (name "/HYPERRAM_FPGA0_RWDS") (class "Default")
      (node (ref "U14") (pin "C2") (pinfunction "IO_L2P_T0_AD12P_35_C2") (pintype "output"))
    )
    (net (code "171") (name "/INITB_F0") (class "Default")
      (node (ref "DS3") (pin "1") (pinfunction "A_1") (pintype "passive"))
      (node (ref "Q3") (pin "3") (pinfunction "DRAIN_3") (pintype "passive"))
    )
    (net (code "172") (name "/JTAG_TCK_FPGA0") (class "Default")
      (node (ref "U14") (pin "V12") (pinfunction "TCK_0_V12") (pintype "input"))
    )
    (net (code "173") (name "/JTAG_TDI_FPGA0") (class "Default")
      (node (ref "U14") (pin "R13") (pinfunction "TDI_0_R13") (pintype "input"))
    )
    (net (code "174") (name "/JTAG_TDO_FPGA0") (class "Default")
      (node (ref "U14") (pin "U13") (pinfunction "TDO_0_U13") (pintype "output"))
    )
    (net (code "175") (name "/JTAG_TMS_FPGA0") (class "Default")
      (node (ref "U14") (pin "T13") (pinfunction "TMS_0_T13") (pintype "input"))
    )
    (net (code "176") (name "/MCU_FPGA0_IO0") (class "Default")
      (node (ref "U14") (pin "U20") (pinfunction "IO_L11P_T1_SRCC_14_U20") (pintype "bidirectional"))
    )
    (net (code "177") (name "/MCU_FPGA0_IO1") (class "Default")
      (node (ref "U14") (pin "V20") (pinfunction "IO_L11N_T1_SRCC_14_V20") (pintype "bidirectional"))
    )
    (net (code "178") (name "/MCU_FPGA0_IO2") (class "Default")
      (node (ref "U14") (pin "W22") (pinfunction "IO_L7N_T1_D10_14_W22") (pintype "bidirectional"))
    )
    (net (code "179") (name "/MCU_FPGA0_IO3") (class "Default")
      (node (ref "U14") (pin "Y22") (pinfunction "IO_L9N_T1_DQS_D13_14_Y22") (pintype "bidirectional"))
    )
    (net (code "180") (name "/MCU_FPGA0_IO4") (class "Default")
      (node (ref "U14") (pin "Y21") (pinfunction "IO_L9P_T1_DQS_14_Y21") (pintype "bidirectional"))
    )
    (net (code "181") (name "/MCU_FPGA0_IO5") (class "Default")
      (node (ref "U14") (pin "AA21") (pinfunction "IO_L8N_T1_D12_14_AA21") (pintype "bidirectional"))
    )
    (net (code "182") (name "/MCU_FPGA0_IO6") (class "Default")
      (node (ref "U14") (pin "AB22") (pinfunction "IO_L10N_T1_D15_14_AB22") (pintype "bidirectional"))
    )
    (net (code "183") (name "/MCU_FPGA0_IO7") (class "Default")
      (node (ref "U14") (pin "AB21") (pinfunction "IO_L10P_T1_D14_14_AB21") (pintype "bidirectional"))
    )
    (net (code "184") (name "/MCU_FPGA0_IO8") (class "Default")
      (node (ref "U14") (pin "AA20") (pinfunction "IO_L8P_T1_D11_14_AA20") (pintype "bidirectional"))
    )
    (net (code "186") (name "/PDONE_F0") (class "Default")
      (node (ref "DS4") (pin "2") (pinfunction "K_2") (pintype "passive"))
      (node (ref "Q4") (pin "3") (pinfunction "D_3") (pintype "passive"))
    )
    (net (code "187") (name "/SMC_ADC_TSNS_FPGA0") (class "Default")
      (node (ref "U15") (pin "2") (pinfunction "VOUT_2") (pintype "output"))
    )
    (net (code "188") (name "/SMC_IO_FPGA0_IO0") (class "Default")
      (node (ref "U14") (pin "T21") (pinfunction "IO_L4P_T0_D04_14_T21") (pintype "bidirectional"))
    )
    (net (code "189") (name "/SMC_IO_FPGA0_IO1") (class "Default")
      (node (ref "U14") (pin "U21") (pinfunction "IO_L4N_T0_D05_14_U21") (pintype "bidirectional"))
    )
    (net (code "190") (name "/SMC_SPI_FPGA0_CLK") (class "Default")
      (node (ref "U14") (pin "W19") (pinfunction "IO_L12P_T1_MRCC_14_W19") (pintype "bidirectional"))
    )
    (net (code "191") (name "/SMC_SPI_FPGA0_CS") (class "Default")
      (node (ref "U14") (pin "AB20") (pinfunction "IO_L15N_T2_DQS_DOUT_CSO_B_14_AB20") (pintype "bidirectional"))
    )
    (net (code "192") (name "/SMC_SPI_FPGA0_RX") (class "Default")
      (node (ref "U14") (pin "AA19") (pinfunction "IO_L15P_T2_DQS_RDWR_B_14_AA19") (pintype "input"))
    )
    (net (code "193") (name "/SMC_SPI_FPGA0_TX") (class "Default")
      (node (ref "U14") (pin "V19") (pinfunction "IO_L14N_T2_SRCC_14_V19") (pintype "output"))
    )
    (net (code "194") (name "/UART_RX_FPGA0") (class "Default")
      (node (ref "U14") (pin "R21") (pinfunction "IO_L2N_T0_D03_14_R21") (pintype "output"))
    )
    (net (code "195") (name "/UART_TX_FPGA0") (class "Default")
      (node (ref "U14") (pin "P21") (pinfunction "IO_L2P_T0_D02_14_P21") (pintype "input"))
    )
    (net (code "196") (name "/USER_FPGA0_BUTTON0") (class "Default")
      (node (ref "U14") (pin "R17") (pinfunction "IO_L24N_T3_A00_D16_14_R17") (pintype "bidirectional"))
    )
    (net (code "197") (name "/USER_FPGA0_BUTTON1") (class "Default")
      (node (ref "U14") (pin "U17") (pinfunction "IO_L18P_T2_A12_D28_14_U17") (pintype "bidirectional"))
    )
    (net (code "198") (name "/USER_FPGA0_BUTTON2") (class "Default")
      (node (ref "U14") (pin "U18") (pinfunction "IO_L18N_T2_A11_D27_14_U18") (pintype "bidirectional"))
    )
    (net (code "199") (name "/USER_FPGA0_BUTTON3") (class "Default")
      (node (ref "U14") (pin "AB18") (pinfunction "IO_L17N_T2_A13_D29_14_AB18") (pintype "bidirectional"))
    )
    (net (code "201") (name "/USER_IO_FPGA0_IO0") (class "Default")
      (node (ref "U14") (pin "V5") (pinfunction "IO_L16N_T2_34_V5") (pintype "bidirectional"))
    )
    (net (code "202") (name "/USER_IO_FPGA0_IO1") (class "Default")
      (node (ref "U14") (pin "U6") (pinfunction "IO_L16P_T2_34_U6") (pintype "bidirectional"))
    )
    (net (code "203") (name "/USER_IO_FPGA0_IO2") (class "Default")
      (node (ref "U14") (pin "V7") (pinfunction "IO_L19P_T3_34_V7") (pintype "bidirectional"))
    )
    (net (code "204") (name "/USER_IO_FPGA0_IO3") (class "Default")
      (node (ref "U14") (pin "V9") (pinfunction "IO_L21P_T3_DQS_34_V9") (pintype "bidirectional"))
    )
    (net (code "205") (name "/USER_IO_FPGA0_IO4") (class "Default")
      (node (ref "U14") (pin "V8") (pinfunction "IO_L21N_T3_DQS_34_V8") (pintype "bidirectional"))
    )
    (net (code "206") (name "/USER_IO_FPGA0_IO5") (class "Default")
      (node (ref "U14") (pin "W9") (pinfunction "IO_L24P_T3_34_W9") (pintype "bidirectional"))
    )
    (net (code "207") (name "/USER_IO_FPGA0_IO6") (class "Default")
      (node (ref "U14") (pin "W6") (pinfunction "IO_L15P_T2_DQS_34_W6") (pintype "bidirectional"))
    )
    (net (code "208") (name "/USER_IO_FPGA0_IO7") (class "Default")
      (node (ref "U14") (pin "Y9") (pinfunction "IO_L24N_T3_34_Y9") (pintype "bidirectional"))
    )
    (net (code "209") (name "/USER_IO_FPGA0_IO8") (class "Default")
      (node (ref "U14") (pin "W7") (pinfunction "IO_L19N_T3_VREF_34_W7") (pintype "bidirectional"))
    )
    (net (code "210") (name "/USER_IO_FPGA0_IO9") (class "Default")
      (node (ref "U14") (pin "Y8") (pinfunction "IO_L23P_T3_34_Y8") (pintype "bidirectional"))
    )
    (net (code "211") (name "/USER_IO_FPGA0_IO10") (class "Default")
      (node (ref "U14") (pin "Y7") (pinfunction "IO_L23N_T3_34_Y7") (pintype "bidirectional"))
    )
    (net (code "212") (name "/USER_IO_FPGA0_IO11") (class "Default")
      (node (ref "U14") (pin "AA8") (pinfunction "IO_L22P_T3_34_AA8") (pintype "bidirectional"))
    )
    (net (code "213") (name "/USER_IO_FPGA0_IO12") (class "Default")
      (node (ref "U14") (pin "AB8") (pinfunction "IO_L22N_T3_34_AB8") (pintype "bidirectional"))
    )
    (net (code "214") (name "/USER_IO_FPGA0_IO13") (class "Default")
      (node (ref "U14") (pin "Y6") (pinfunction "IO_L18P_T2_34_Y6") (pintype "bidirectional"))
    )
    (net (code "215") (name "/USER_IO_FPGA0_IO14") (class "Default")
      (node (ref "U14") (pin "AB7") (pinfunction "IO_L20P_T3_34_AB7") (pintype "bidirectional"))
    )
    (net (code "216") (name "/USER_IO_FPGA0_IO15") (class "Default")
      (node (ref "U14") (pin "AA6") (pinfunction "IO_L18N_T2_34_AA6") (pintype "bidirectional"))
    )
    (net (code "217") (name "/USER_IO_FPGA0_IO16") (class "Default")
      (node (ref "U14") (pin "AB6") (pinfunction "IO_L20N_T3_34_AB6") (pintype "bidirectional"))
    )
    (net (code "218") (name "/USER_IO_FPGA0_IO17") (class "Default")
      (node (ref "U14") (pin "W5") (pinfunction "IO_L15N_T2_DQS_34_W5") (pintype "bidirectional"))
    )
    (net (code "219") (name "/USER_IO_FPGA0_IO18") (class "Default")
      (node (ref "U14") (pin "AB5") (pinfunction "IO_L10N_T1_34_AB5") (pintype "bidirectional"))
    )
    (net (code "220") (name "/USER_IO_FPGA0_IO19") (class "Default")
      (node (ref "U14") (pin "AA5") (pinfunction "IO_L10P_T1_34_AA5") (pintype "bidirectional"))
    )
    (net (code "221") (name "/USER_IO_FPGA0_IO20") (class "Default")
      (node (ref "U14") (pin "Y4") (pinfunction "IO_L11P_T1_SRCC_34_Y4") (pintype "bidirectional"))
    )
    (net (code "222") (name "/USER_IO_FPGA0_IO21") (class "Default")
      (node (ref "U14") (pin "AA4") (pinfunction "IO_L11N_T1_SRCC_34_AA4") (pintype "bidirectional"))
    )
    (net (code "223") (name "/USER_IO_FPGA0_IO22") (class "Default")
      (node (ref "U14") (pin "W4") (pinfunction "IO_L12N_T1_MRCC_34_W4") (pintype "bidirectional"))
    )
    (net (code "224") (name "/USER_IO_FPGA0_IO23") (class "Default")
      (node (ref "U14") (pin "AB3") (pinfunction "IO_L8P_T1_34_AB3") (pintype "bidirectional"))
    )
    (net (code "225") (name "/USER_IO_FPGA0_IO24") (class "Default")
      (node (ref "U14") (pin "AA3") (pinfunction "IO_L9N_T1_DQS_34_AA3") (pintype "bidirectional"))
    )
    (net (code "226") (name "/USER_IO_FPGA0_IO25") (class "Default")
      (node (ref "U14") (pin "AB2") (pinfunction "IO_L8N_T1_34_AB2") (pintype "bidirectional"))
    )
    (net (code "227") (name "/USER_IO_FPGA0_IO26") (class "Default")
      (node (ref "U14") (pin "Y3") (pinfunction "IO_L9P_T1_DQS_34_Y3") (pintype "bidirectional"))
    )
    (net (code "228") (name "/USER_IO_FPGA0_IO27") (class "Default")
      (node (ref "U14") (pin "AB1") (pinfunction "IO_L7N_T1_34_AB1") (pintype "bidirectional"))
    )
    (net (code "229") (name "/USER_IO_FPGA0_IO28") (class "Default")
      (node (ref "U14") (pin "Y2") (pinfunction "IO_L4N_T0_34_Y2") (pintype "bidirectional"))
    )
    (net (code "230") (name "/USER_IO_FPGA0_IO29") (class "Default")
      (node (ref "U14") (pin "AA1") (pinfunction "IO_L7P_T1_34_AA1") (pintype "bidirectional"))
    )
    (net (code "231") (name "/USER_IO_FPGA0_IO30") (class "Default")
      (node (ref "U14") (pin "V4") (pinfunction "IO_L12P_T1_MRCC_34_V4") (pintype "bidirectional"))
    )
    (net (code "232") (name "/USER_IO_FPGA0_IO31") (class "Default")
      (node (ref "U14") (pin "Y1") (pinfunction "IO_L5N_T0_34_Y1") (pintype "bidirectional"))
    )
    (net (code "233") (name "/USER_IO_FPGA0_IO32") (class "Default")
      (node (ref "U14") (pin "W2") (pinfunction "IO_L4P_T0_34_W2") (pintype "bidirectional"))
    )
    (net (code "234") (name "/USER_IO_FPGA0_IO33") (class "Default")
      (node (ref "U14") (pin "W1") (pinfunction "IO_L5P_T0_34_W1") (pintype "bidirectional"))
    )
    (net (code "235") (name "/USER_IO_FPGA0_IO34") (class "Default")
      (node (ref "U14") (pin "V3") (pinfunction "IO_L6N_T0_VREF_34_V3") (pintype "bidirectional"))
    )
    (net (code "236") (name "/USER_IO_FPGA0_IO35") (class "Default")
      (node (ref "U14") (pin "V2") (pinfunction "IO_L2N_T0_34_V2") (pintype "bidirectional"))
    )
    (net (code "237") (name "/USER_IO_FPGA0_IO36") (class "Default")
      (node (ref "U14") (pin "U3") (pinfunction "IO_L6P_T0_34_U3") (pintype "bidirectional"))
    )
    (net (code "238") (name "/USER_IO_FPGA0_IO37") (class "Default")
      (node (ref "U14") (pin "U2") (pinfunction "IO_L2P_T0_34_U2") (pintype "bidirectional"))
    )
    (net (code "239") (name "/USER_IO_FPGA0_IO38") (class "Default")
      (node (ref "U14") (pin "U1") (pinfunction "IO_L1N_T0_34_U1") (pintype "bidirectional"))
    )
    (net (code "240") (name "/USER_IO_FPGA0_IO39") (class "Default")
      (node (ref "U14") (pin "U5") (pinfunction "IO_L14N_T2_SRCC_34_U5") (pintype "bidirectional"))
    )
    (net (code "241") (name "/USER_IO_FPGA0_IO40") (class "Default")
      (node (ref "U14") (pin "R6") (pinfunction "IO_L17P_T2_34_R6") (pintype "bidirectional"))
    )
    (net (code "242") (name "/USER_IO_FPGA0_IO41") (class "Default")
      (node (ref "U14") (pin "T6") (pinfunction "IO_L17N_T2_34_T6") (pintype "bidirectional"))
    )
    (net (code "243") (name "/USER_IO_FPGA0_IO42") (class "Default")
      (node (ref "U14") (pin "T5") (pinfunction "IO_L14P_T2_SRCC_34_T5") (pintype "bidirectional"))
    )
    (net (code "244") (name "/USER_IO_FPGA0_IO43") (class "Default")
      (node (ref "U14") (pin "R4") (pinfunction "IO_L13P_T2_MRCC_34_R4") (pintype "bidirectional"))
    )
    (net (code "245") (name "/USER_IO_FPGA0_IO44") (class "Default")
      (node (ref "U14") (pin "R3") (pinfunction "IO_L3P_T0_DQS_34_R3") (pintype "bidirectional"))
    )
    (net (code "246") (name "/USER_IO_FPGA0_IO45") (class "Default")
      (node (ref "U14") (pin "R2") (pinfunction "IO_L3N_T0_DQS_34_R2") (pintype "bidirectional"))
    )
    (net (code "247") (name "/USER_IO_FPGA0_IO46") (class "Default")
      (node (ref "U14") (pin "T4") (pinfunction "IO_L13N_T2_MRCC_34_T4") (pintype "bidirectional"))
    )
    (net (code "248") (name "/USER_IO_FPGA0_IO47") (class "Default")
      (node (ref "U14") (pin "T1") (pinfunction "IO_L1P_T0_34_T1") (pintype "bidirectional"))
    )
    (net (code "250") (name "/USER_PMOD0_FPGA0_LVIO0") (class "Default")
      (node (ref "U14") (pin "L5") (pinfunction "IO_L18P_T2_35_L5") (pintype "bidirectional"))
    )
    (net (code "251") (name "/USER_PMOD0_FPGA0_LVIO1") (class "Default")
      (node (ref "U14") (pin "K6") (pinfunction "IO_L17P_T2_35_K6") (pintype "bidirectional"))
    )
    (net (code "252") (name "/USER_PMOD0_FPGA0_LVIO2") (class "Default")
      (node (ref "U14") (pin "L4") (pinfunction "IO_L18N_T2_35_L4") (pintype "bidirectional"))
    )
    (net (code "253") (name "/USER_PMOD0_FPGA0_LVIO3") (class "Default")
      (node (ref "U14") (pin "M6") (pinfunction "IO_L23P_T3_35_M6") (pintype "bidirectional"))
    )
    (net (code "254") (name "/USER_PMOD0_FPGA0_LVIO4") (class "Default")
      (node (ref "U14") (pin "M5") (pinfunction "IO_L23N_T3_35_M5") (pintype "bidirectional"))
    )
    (net (code "255") (name "/USER_PMOD0_FPGA0_LVIO5") (class "Default")
      (node (ref "U14") (pin "N5") (pinfunction "IO_L24N_T3_35_N5") (pintype "bidirectional"))
    )
    (net (code "256") (name "/USER_PMOD0_FPGA0_LVIO6") (class "Default")
      (node (ref "U14") (pin "P6") (pinfunction "IO_L24P_T3_35_P6") (pintype "bidirectional"))
    )
    (net (code "257") (name "/USER_PMOD0_FPGA0_LVIO7") (class "Default")
      (node (ref "U14") (pin "M3") (pinfunction "IO_L16P_T2_35_M3") (pintype "bidirectional"))
    )
    (net (code "259") (name "/USER_PMOD1_FPGA0_LVIO0") (class "Default")
      (node (ref "U14") (pin "P4") (pinfunction "IO_L21N_T3_DQS_35_P4") (pintype "bidirectional"))
    )
    (net (code "260") (name "/USER_PMOD1_FPGA0_LVIO1") (class "Default")
      (node (ref "U14") (pin "P5") (pinfunction "IO_L21P_T3_DQS_35_P5") (pintype "bidirectional"))
    )
    (net (code "261") (name "/USER_PMOD1_FPGA0_LVIO2") (class "Default")
      (node (ref "U14") (pin "P2") (pinfunction "IO_L22P_T3_35_P2") (pintype "bidirectional"))
    )
    (net (code "262") (name "/USER_PMOD1_FPGA0_LVIO3") (class "Default")
      (node (ref "U14") (pin "R1") (pinfunction "IO_L20P_T3_35_R1") (pintype "bidirectional"))
    )
    (net (code "263") (name "/USER_PMOD1_FPGA0_LVIO4") (class "Default")
      (node (ref "U14") (pin "N3") (pinfunction "IO_L19N_T3_VREF_35_N3") (pintype "bidirectional"))
    )
    (net (code "264") (name "/USER_PMOD1_FPGA0_LVIO5") (class "Default")
      (node (ref "U14") (pin "P1") (pinfunction "IO_L20N_T3_35_P1") (pintype "bidirectional"))
    )
    (net (code "265") (name "/USER_PMOD1_FPGA0_LVIO6") (class "Default")
      (node (ref "U14") (pin "N2") (pinfunction "IO_L22N_T3_35_N2") (pintype "bidirectional"))
    )
    (net (code "266") (name "/USER_PMOD1_FPGA0_LVIO7") (class "Default")
      (node (ref "U14") (pin "N4") (pinfunction "IO_L19P_T3_35_N4") (pintype "bidirectional"))
    )
    (net (code "268") (name "/USER_PMOD2_FPGA0_LVIO0") (class "Default")
      (node (ref "U14") (pin "L3") (pinfunction "IO_L14P_T2_SRCC_35_L3") (pintype "bidirectional"))
    )
    (net (code "269") (name "/USER_PMOD2_FPGA0_LVIO1") (class "Default")
      (node (ref "U14") (pin "M2") (pinfunction "IO_L16N_T2_35_M2") (pintype "bidirectional"))
    )
    (net (code "270") (name "/USER_PMOD2_FPGA0_LVIO2") (class "Default")
      (node (ref "U14") (pin "M1") (pinfunction "IO_L15P_T2_DQS_35_M1") (pintype "bidirectional"))
    )
    (net (code "271") (name "/USER_PMOD2_FPGA0_LVIO3") (class "Default")
      (node (ref "U14") (pin "K3") (pinfunction "IO_L14N_T2_SRCC_35_K3") (pintype "bidirectional"))
    )
    (net (code "272") (name "/USER_PMOD2_FPGA0_LVIO4") (class "Default")
      (node (ref "U14") (pin "L1") (pinfunction "IO_L15N_T2_DQS_35_L1") (pintype "bidirectional"))
    )
    (net (code "273") (name "/USER_PMOD2_FPGA0_LVIO5") (class "Default")
      (node (ref "U14") (pin "K2") (pinfunction "IO_L9P_T1_DQS_AD7P_35_K2") (pintype "bidirectional"))
    )
    (net (code "274") (name "/USER_PMOD2_FPGA0_LVIO6") (class "Default")
      (node (ref "U14") (pin "K1") (pinfunction "IO_L7P_T1_AD6P_35_K1") (pintype "bidirectional"))
    )
    (net (code "275") (name "/USER_PMOD2_FPGA0_LVIO7") (class "Default")
      (node (ref "U14") (pin "K4") (pinfunction "IO_L13P_T2_MRCC_35_K4") (pintype "bidirectional"))
    )
    (net (code "277") (name "/USER_PMOD3_FPGA0_LVIO0") (class "Default")
      (node (ref "U14") (pin "J2") (pinfunction "IO_L9N_T1_DQS_AD7N_35_J2") (pintype "bidirectional"))
    )
    (net (code "278") (name "/USER_PMOD3_FPGA0_LVIO1") (class "Default")
      (node (ref "U14") (pin "J1") (pinfunction "IO_L7N_T1_AD6N_35_J1") (pintype "bidirectional"))
    )
    (net (code "279") (name "/USER_PMOD3_FPGA0_LVIO2") (class "Default")
      (node (ref "U14") (pin "J4") (pinfunction "IO_L13N_T2_MRCC_35_J4") (pintype "bidirectional"))
    )
    (net (code "280") (name "/USER_PMOD3_FPGA0_LVIO3") (class "Default")
      (node (ref "U14") (pin "H2") (pinfunction "IO_L8P_T1_AD14P_35_H2") (pintype "bidirectional"))
    )
    (net (code "281") (name "/USER_PMOD3_FPGA0_LVIO4") (class "Default")
      (node (ref "U14") (pin "J5") (pinfunction "IO_L10P_T1_AD15P_35_J5") (pintype "bidirectional"))
    )
    (net (code "282") (name "/USER_PMOD3_FPGA0_LVIO5") (class "Default")
      (node (ref "U14") (pin "G2") (pinfunction "IO_L8N_T1_AD14N_35_G2") (pintype "bidirectional"))
    )
    (net (code "283") (name "/USER_PMOD3_FPGA0_LVIO6") (class "Default")
      (node (ref "U14") (pin "J6") (pinfunction "IO_L17N_T2_35_J6") (pintype "bidirectional"))
    )
    (net (code "284") (name "/USER_PMOD3_FPGA0_LVIO7") (class "Default")
      (node (ref "U14") (pin "H5") (pinfunction "IO_L10N_T1_AD15N_35_H5") (pintype "bidirectional"))
    )
    (net (code "286") (name "GND") (class "Default")
      (node (ref "C134") (pin "1") (pinfunction "1_1") (pintype "passive"))
      (node (ref "C136") (pin "1") (pinfunction "1_1") (pintype "passive"))
      (node (ref "C137") (pin "1") (pinfunction "1_1") (pintype "passive"))
      (node (ref "C140") (pin "1") (pinfunction "1_1") (pintype "passive"))
      (node (ref "C141") (pin "1") (pinfunction "1_1") (pintype "passive"))
      (node (ref "C142") (pin "1") (pinfunction "1_1") (pintype "passive"))
      (node (ref "C143") (pin "1") (pinfunction "1_1") (pintype "passive"))
      (node (ref "C144") (pin "1") (pinfunction "1_1") (pintype "passive"))
      (node (ref "C145") (pin "1") (pinfunction "1_1") (pintype "passive"))
      (node (ref "C146") (pin "1") (pinfunction "1_1") (pintype "passive"))
      (node (ref "C147") (pin "1") (pinfunction "1_1") (pintype "passive"))
      (node (ref "C148") (pin "1") (pinfunction "1_1") (pintype "passive"))
      (node (ref "C149") (pin "1") (pinfunction "1_1") (pintype "passive"))
      (node (ref "C150") (pin "1") (pinfunction "1_1") (pintype "passive"))
      (node (ref "C151") (pin "1") (pinfunction "1_1") (pintype "passive"))
      (node (ref "C152") (pin "1") (pinfunction "1_1") (pintype "passive"))
      (node (ref "C153") (pin "1") (pinfunction "1_1") (pintype "passive"))
      (node (ref "C154") (pin "1") (pinfunction "1_1") (pintype "passive"))
      (node (ref "C155") (pin "1") (pinfunction "1_1") (pintype "passive"))
      (node (ref "C156") (pin "1") (pinfunction "1_1") (pintype "passive"))
      (node (ref "C157") (pin "1") (pinfunction "1_1") (pintype "passive"))
      (node (ref "C158") (pin "1") (pinfunction "1_1") (pintype "passive"))
      (node (ref "C159") (pin "1") (pinfunction "1_1") (pintype "passive"))
      (node (ref "C160") (pin "1") (pinfunction "1_1") (pintype "passive"))
      (node (ref "C161") (pin "1") (pinfunction "1_1") (pintype "passive"))
      (node (ref "C162") (pin "1") (pinfunction "1_1") (pintype "passive"))
      (node (ref "C163") (pin "1") (pinfunction "1_1") (pintype "passive"))
      (node (ref "C164") (pin "1") (pinfunction "1_1") (pintype "passive"))
      (node (ref "C165") (pin "1") (pinfunction "1_1") (pintype "passive"))
      (node (ref "C166") (pin "1") (pinfunction "1_1") (pintype "passive"))
      (node (ref "C167") (pin "1") (pinfunction "1_1") (pintype "passive"))
      (node (ref "C168") (pin "1") (pinfunction "1_1") (pintype "passive"))
      (node (ref "C169") (pin "1") (pinfunction "1_1") (pintype "passive"))
      (node (ref "C170") (pin "1") (pinfunction "1_1") (pintype "passive"))
      (node (ref "C171") (pin "1") (pinfunction "1_1") (pintype "passive"))
      (node (ref "C172") (pin "1") (pinfunction "1_1") (pintype "passive"))
      (node (ref "C173") (pin "1") (pinfunction "1_1") (pintype "passive"))
      (node (ref "C174") (pin "1") (pinfunction "1_1") (pintype "passive"))
      (node (ref "C175") (pin "1") (pinfunction "1_1") (pintype "passive"))
      (node (ref "C176") (pin "1") (pinfunction "1_1") (pintype "passive"))
      (node (ref "C177") (pin "1") (pinfunction "1_1") (pintype "passive"))
      (node (ref "C178") (pin "1") (pinfunction "1_1") (pintype "passive"))
      (node (ref "C179") (pin "1") (pinfunction "1_1") (pintype "passive"))
      (node (ref "C180") (pin "1") (pinfunction "1_1") (pintype "passive"))
      (node (ref "C181") (pin "1") (pinfunction "1_1") (pintype "passive"))
      (node (ref "C182") (pin "1") (pinfunction "1_1") (pintype "passive"))
      (node (ref "C183") (pin "1") (pinfunction "1_1") (pintype "passive"))
      (node (ref "C184") (pin "1") (pinfunction "1_1") (pintype "passive"))
      (node (ref "C185") (pin "1") (pinfunction "1_1") (pintype "passive"))
      (node (ref "C186") (pin "1") (pinfunction "1_1") (pintype "passive"))
      (node (ref "C187") (pin "1") (pinfunction "1_1") (pintype "passive"))
      (node (ref "C188") (pin "1") (pinfunction "1_1") (pintype "passive"))
      (node (ref "C189") (pin "1") (pinfunction "1_1") (pintype "passive"))
      (node (ref "C190") (pin "1") (pinfunction "1_1") (pintype "passive"))
      (node (ref "C191") (pin "1") (pinfunction "1_1") (pintype "passive"))
      (node (ref "C192") (pin "1") (pinfunction "1_1") (pintype "passive"))
      (node (ref "C193") (pin "1") (pinfunction "1_1") (pintype "passive"))
      (node (ref "C194") (pin "1") (pinfunction "1_1") (pintype "passive"))
      (node (ref "C195") (pin "1") (pinfunction "1_1") (pintype "passive"))
      (node (ref "C196") (pin "1") (pinfunction "1_1") (pintype "passive"))
      (node (ref "C198") (pin "1") (pinfunction "1_1") (pintype "passive"))
      (node (ref "C199") (pin "1") (pinfunction "1_1") (pintype "passive"))
      (node (ref "C200") (pin "1") (pinfunction "1_1") (pintype "passive"))
      (node (ref "C201") (pin "1") (pinfunction "1_1") (pintype "passive"))
      (node (ref "C202") (pin "1") (pinfunction "1_1") (pintype "passive"))
      (node (ref "C203") (pin "1") (pinfunction "1_1") (pintype "passive"))
      (node (ref "C204") (pin "1") (pinfunction "1_1") (pintype "passive"))
      (node (ref "C205") (pin "1") (pinfunction "1_1") (pintype "passive"))
      (node (ref "C206") (pin "1") (pinfunction "1_1") (pintype "passive"))
      (node (ref "C207") (pin "1") (pinfunction "1_1") (pintype "passive"))
      (node (ref "C208") (pin "1") (pinfunction "1_1") (pintype "passive"))
      (node (ref "C209") (pin "1") (pinfunction "1_1") (pintype "passive"))
      (node (ref "C210") (pin "1") (pinfunction "1_1") (pintype "passive"))
      (node (ref "C211") (pin "1") (pinfunction "1_1") (pintype "passive"))
      (node (ref "C212") (pin "1") (pinfunction "1_1") (pintype "passive"))
      (node (ref "C213") (pin "1") (pinfunction "1_1") (pintype "passive"))
      (node (ref "C214") (pin "1") (pinfunction "1_1") (pintype "passive"))
      (node (ref "C215") (pin "1") (pinfunction "1_1") (pintype "passive"))
      (node (ref "C216") (pin "1") (pinfunction "1_1") (pintype "passive"))
      (node (ref "C217") (pin "1") (pinfunction "1_1") (pintype "passive"))
      (node (ref "C218") (pin "1") (pinfunction "1_1") (pintype "passive"))
      (node (ref "C219") (pin "1") (pinfunction "1_1") (pintype "passive"))
      (node (ref "C220") (pin "1") (pinfunction "1_1") (pintype "passive"))
      (node (ref "C221") (pin "1") (pinfunction "1_1") (pintype "passive"))
      (node (ref "C222") (pin "1") (pinfunction "1_1") (pintype "passive"))
      (node (ref "C223") (pin "1") (pinfunction "1_1") (pintype "passive"))
      (node (ref "C224") (pin "1") (pinfunction "1_1") (pintype "passive"))
      (node (ref "C225") (pin "1") (pinfunction "1_1") (pintype "passive"))
      (node (ref "C226") (pin "1") (pinfunction "1_1") (pintype "passive"))
      (node (ref "C227") (pin "1") (pinfunction "1_1") (pintype "passive"))
      (node (ref "C228") (pin "1") (pinfunction "1_1") (pintype "passive"))
      (node (ref "C342") (pin "1") (pinfunction "1_1") (pintype "passive"))
      (node (ref "C343") (pin "1") (pinfunction "1_1") (pintype "passive"))
      (node (ref "L6") (pin "1") (pinfunction "1_1") (pintype "passive"))
      (node (ref "Q4") (pin "2") (pinfunction "S_2") (pintype "passive"))
      (node (ref "R64") (pin "1") (pinfunction "1_1") (pintype "passive"))
      (node (ref "SW6") (pin "1") (pinfunction "1_1") (pintype "passive"))
      (node (ref "SW6") (pin "2") (pinfunction "2_2") (pintype "passive"))
      (node (ref "SW7") (pin "1") (pinfunction "1_1") (pintype "passive"))
      (node (ref "SW7") (pin "2") (pinfunction "2_2") (pintype "passive"))
      (node (ref "SW8") (pin "4") (pinfunction "4_4") (pintype "passive"))
      (node (ref "SW8") (pin "5") (pinfunction "5_5") (pintype "passive"))
      (node (ref "SW8") (pin "6") (pinfunction "6_6") (pintype "passive"))
      (node (ref "U14") (pin "A11") (pinfunction "GND_A11") (pintype "power_in"))
      (node (ref "U14") (pin "A12") (pinfunction "GND_A12") (pintype "power_in"))
      (node (ref "U14") (pin "A2") (pinfunction "GND_A2") (pintype "power_in"))
      (node (ref "U14") (pin "A22") (pinfunction "GND_A22") (pintype "power_in"))
      (node (ref "U14") (pin "A3") (pinfunction "GND_A3") (pintype "power_in"))
      (node (ref "U14") (pin "A5") (pinfunction "GND_A5") (pintype "power_in"))
      (node (ref "U14") (pin "A7") (pinfunction "GND_A7") (pintype "power_in"))
      (node (ref "U14") (pin "A9") (pinfunction "GND_A9") (pintype "power_in"))
      (node (ref "U14") (pin "AA12") (pinfunction "GND_AA12") (pintype "power_in"))
      (node (ref "U14") (pin "AA2") (pinfunction "GND_AA2") (pintype "power_in"))
      (node (ref "U14") (pin "AA22") (pinfunction "GND_AA22") (pintype "power_in"))
      (node (ref "U14") (pin "AB19") (pinfunction "GND_AB19") (pintype "power_in"))
      (node (ref "U14") (pin "AB9") (pinfunction "GND_AB9") (pintype "power_in"))
      (node (ref "U14") (pin "B12") (pinfunction "GND_B12") (pintype "power_in"))
      (node (ref "U14") (pin "B19") (pinfunction "GND_B19") (pintype "power_in"))
      (node (ref "U14") (pin "B3") (pinfunction "GND_B3") (pintype "power_in"))
      (node (ref "U14") (pin "C10") (pinfunction "GND_C10") (pintype "power_in"))
      (node (ref "U14") (pin "C12") (pinfunction "GND_C12") (pintype "power_in"))
      (node (ref "U14") (pin "C16") (pinfunction "GND_C16") (pintype "power_in"))
      (node (ref "U14") (pin "C3") (pinfunction "GND_C3") (pintype "power_in"))
      (node (ref "U14") (pin "C6") (pinfunction "GND_C6") (pintype "power_in"))
      (node (ref "U14") (pin "D12") (pinfunction "GND_D12") (pintype "power_in"))
      (node (ref "U14") (pin "D13") (pinfunction "GND_D13") (pintype "power_in"))
      (node (ref "U14") (pin "D3") (pinfunction "GND_D3") (pintype "power_in"))
      (node (ref "U14") (pin "D4") (pinfunction "GND_D4") (pintype "power_in"))
      (node (ref "U14") (pin "D8") (pinfunction "GND_D8") (pintype "power_in"))
      (node (ref "U14") (pin "E11") (pinfunction "GND_E11") (pintype "power_in"))
      (node (ref "U14") (pin "E20") (pinfunction "GND_E20") (pintype "power_in"))
      (node (ref "U14") (pin "E4") (pinfunction "GND_E4") (pintype "power_in"))
      (node (ref "U14") (pin "E5") (pinfunction "GND_E5") (pintype "power_in"))
      (node (ref "U14") (pin "E7") (pinfunction "GND_E7") (pintype "power_in"))
      (node (ref "U14") (pin "E9") (pinfunction "GND_E9") (pintype "power_in"))
      (node (ref "U14") (pin "F11") (pinfunction "GND_F11") (pintype "power_in"))
      (node (ref "U14") (pin "F17") (pinfunction "GND_F17") (pintype "power_in"))
      (node (ref "U14") (pin "F5") (pinfunction "GND_F5") (pintype "power_in"))
      (node (ref "U14") (pin "G10") (pinfunction "GND_G10") (pintype "power_in"))
      (node (ref "U14") (pin "G12") (pinfunction "GND_G12") (pintype "power_in"))
      (node (ref "U14") (pin "G14") (pinfunction "GND_G14") (pintype "power_in"))
      (node (ref "U14") (pin "G5") (pinfunction "GND_G5") (pintype "power_in"))
      (node (ref "U14") (pin "G6") (pinfunction "GND_G6") (pintype "power_in"))
      (node (ref "U14") (pin "G7") (pinfunction "GND_G7") (pintype "power_in"))
      (node (ref "U14") (pin "G8") (pinfunction "GND_G8") (pintype "power_in"))
      (node (ref "U14") (pin "G9") (pinfunction "GND_G9") (pintype "power_in"))
      (node (ref "U14") (pin "H1") (pinfunction "GND_H1") (pintype "power_in"))
      (node (ref "U14") (pin "H11") (pinfunction "GND_H11") (pintype "power_in"))
      (node (ref "U14") (pin "H21") (pinfunction "GND_H21") (pintype "power_in"))
      (node (ref "U14") (pin "H7") (pinfunction "GND_H7") (pintype "power_in"))
      (node (ref "U14") (pin "H9") (pinfunction "GND_H9") (pintype "power_in"))
      (node (ref "U14") (pin "J10") (pinfunction "GND_J10") (pintype "power_in"))
      (node (ref "U14") (pin "J12") (pinfunction "GND_J12") (pintype "power_in"))
      (node (ref "U14") (pin "J18") (pinfunction "GND_J18") (pintype "power_in"))
      (node (ref "U14") (pin "J8") (pinfunction "GND_J8") (pintype "power_in"))
      (node (ref "U14") (pin "K11") (pinfunction "GND_K11") (pintype "power_in"))
      (node (ref "U14") (pin "K15") (pinfunction "GND_K15") (pintype "power_in"))
      (node (ref "U14") (pin "K5") (pinfunction "GND_K5") (pintype "power_in"))
      (node (ref "U14") (pin "K7") (pinfunction "GND_K7") (pintype "power_in"))
      (node (ref "U14") (pin "K9") (pinfunction "GNDADC_0_K9") (pintype "power_in"))
      (node (ref "U14") (pin "L2") (pinfunction "GND_L2") (pintype "power_in"))
      (node (ref "U14") (pin "L22") (pinfunction "GND_L22") (pintype "power_in"))
      (node (ref "U14") (pin "L8") (pinfunction "GND_L8") (pintype "power_in"))
      (node (ref "U14") (pin "M11") (pinfunction "GND_M11") (pintype "power_in"))
      (node (ref "U14") (pin "M19") (pinfunction "GND_M19") (pintype "power_in"))
      (node (ref "U14") (pin "M7") (pinfunction "GND_M7") (pintype "power_in"))
      (node (ref "U14") (pin "N10") (pinfunction "DXP_0_N10") (pintype "input"))
      (node (ref "U14") (pin "N16") (pinfunction "GND_N16") (pintype "power_in"))
      (node (ref "U14") (pin "N6") (pinfunction "GND_N6") (pintype "power_in"))
      (node (ref "U14") (pin "N8") (pinfunction "GND_N8") (pintype "power_in"))
      (node (ref "U14") (pin "N9") (pinfunction "DXN_0_N9") (pintype "input"))
      (node (ref "U14") (pin "P11") (pinfunction "GND_P11") (pintype "power_in"))
      (node (ref "U14") (pin "P13") (pinfunction "GND_P13") (pintype "power_in"))
      (node (ref "U14") (pin "P3") (pinfunction "GND_P3") (pintype "power_in"))
      (node (ref "U14") (pin "P7") (pinfunction "GND_P7") (pintype "power_in"))
      (node (ref "U14") (pin "P9") (pinfunction "GND_P9") (pintype "power_in"))
      (node (ref "U14") (pin "R10") (pinfunction "GND_R10") (pintype "power_in"))
      (node (ref "U14") (pin "R12") (pinfunction "GND_R12") (pintype "power_in"))
      (node (ref "U14") (pin "R20") (pinfunction "GND_R20") (pintype "power_in"))
      (node (ref "U14") (pin "R8") (pinfunction "GND_R8") (pintype "power_in"))
      (node (ref "U14") (pin "T11") (pinfunction "GND_T11") (pintype "power_in"))
      (node (ref "U14") (pin "T17") (pinfunction "GND_T17") (pintype "power_in"))
      (node (ref "U14") (pin "T7") (pinfunction "GND_T7") (pintype "power_in"))
      (node (ref "U14") (pin "T9") (pinfunction "GND_T9") (pintype "power_in"))
      (node (ref "U14") (pin "U14") (pinfunction "GND_U14") (pintype "power_in"))
      (node (ref "U14") (pin "U4") (pinfunction "GND_U4") (pintype "power_in"))
      (node (ref "U14") (pin "V1") (pinfunction "GND_V1") (pintype "power_in"))
      (node (ref "U14") (pin "V11") (pinfunction "GND_V11") (pintype "power_in"))
      (node (ref "U14") (pin "V21") (pinfunction "GND_V21") (pintype "power_in"))
      (node (ref "U14") (pin "W18") (pinfunction "GND_W18") (pintype "power_in"))
      (node (ref "U14") (pin "W8") (pinfunction "GND_W8") (pintype "power_in"))
      (node (ref "U14") (pin "Y15") (pinfunction "GND_Y15") (pintype "power_in"))
      (node (ref "U14") (pin "Y5") (pinfunction "GND_Y5") (pintype "power_in"))
      (node (ref "U15") (pin "3") (pinfunction "VSS_3") (pintype "power_in"))
      (node (ref "U16") (pin "3") (pinfunction "GND_3") (pintype "passive"))
      (node (ref "U17") (pin "3") (pinfunction "GND_3") (pintype "power_in"))
      (node (ref "U18") (pin "4") (pinfunction "GND_4") (pintype "passive"))
      (node (ref "X2") (pin "2") (pinfunction "GND_2") (pintype "passive"))
    )
    (net (code "287") (name "Net-(C142-Pad2)") (class "Default")
      (node (ref "C142") (pin "2") (pinfunction "2_2") (pintype "passive"))
      (node (ref "R60") (pin "1") (pinfunction "1_1") (pintype "passive"))
      (node (ref "R61") (pin "2") (pinfunction "2_2") (pintype "passive"))
      (node (ref "SW6") (pin "3") (pinfunction "3_3") (pintype "passive"))
      (node (ref "SW6") (pin "4") (pinfunction "4_4") (pintype "passive"))
    )
    (net (code "288") (name "Net-(C160-Pad2)") (class "Default")
      (node (ref "C160") (pin "2") (pinfunction "2_2") (pintype "passive"))
      (node (ref "R62") (pin "1") (pinfunction "1_1") (pintype "passive"))
      (node (ref "R63") (pin "2") (pinfunction "2_2") (pintype "passive"))
      (node (ref "SW7") (pin "3") (pinfunction "3_3") (pintype "passive"))
      (node (ref "SW7") (pin "4") (pinfunction "4_4") (pintype "passive"))
    )
    (net (code "289") (name "Net-(DS3-K)") (class "Default")
      (node (ref "DS3") (pin "2") (pinfunction "K_2") (pintype "passive"))
      (node (ref "R64") (pin "2") (pinfunction "2_2") (pintype "passive"))
    )
    (net (code "290") (name "Net-(DS4-A)") (class "Default")
      (node (ref "DS4") (pin "1") (pinfunction "A_1") (pintype "passive"))
      (node (ref "R65") (pin "1") (pinfunction "1_1") (pintype "passive"))
    )
    (net (code "291") (name "Net-(U14G-MGTRREF_216)") (class "Default")
      (node (ref "R52") (pin "2") (pinfunction "2_2") (pintype "passive"))
      (node (ref "U14") (pin "F8") (pinfunction "MGTRREF_216_F8") (pintype "input"))
    )
    (net (code "292") (name "unconnected-(U14A-IO_0_14-PadP20)") (class "Default")
      (node (ref "U14") (pin "P20") (pinfunction "IO_0_14_P20") (pintype "bidirectional+no_connect"))
    )
    (net (code "293") (name "unconnected-(U14A-IO_L3N_T0_DQS_EMCCLK_14-PadV22)") (class "Default")
      (node (ref "U14") (pin "V22") (pinfunction "IO_L3N_T0_DQS_EMCCLK_14_V22") (pintype "bidirectional+no_connect"))
    )
    (net (code "294") (name "unconnected-(U14A-IO_L5N_T0_D07_14-PadR19)") (class "Default")
      (node (ref "U14") (pin "R19") (pinfunction "IO_L5N_T0_D07_14_R19") (pintype "bidirectional+no_connect"))
    )
    (net (code "295") (name "unconnected-(U14A-IO_L5P_T0_D06_14-PadP19)") (class "Default")
      (node (ref "U14") (pin "P19") (pinfunction "IO_L5P_T0_D06_14_P19") (pintype "bidirectional+no_connect"))
    )
    (net (code "296") (name "unconnected-(U14A-IO_L6N_T0_D08_VREF_14-PadT20)") (class "Default")
      (node (ref "U14") (pin "T20") (pinfunction "IO_L6N_T0_D08_VREF_14_T20") (pintype "bidirectional+no_connect"))
    )
    (net (code "297") (name "unconnected-(U14A-IO_L7P_T1_D09_14-PadW21)") (class "Default")
      (node (ref "U14") (pin "W21") (pinfunction "IO_L7P_T1_D09_14_W21") (pintype "bidirectional+no_connect"))
    )
    (net (code "298") (name "unconnected-(U14A-IO_L12N_T1_MRCC_14-PadW20)") (class "Default")
      (node (ref "U14") (pin "W20") (pinfunction "IO_L12N_T1_MRCC_14_W20") (pintype "input+no_connect"))
    )
    (net (code "299") (name "unconnected-(U14A-IO_L13N_T2_MRCC_14-PadY19)") (class "Default")
      (node (ref "U14") (pin "Y19") (pinfunction "IO_L13N_T2_MRCC_14_Y19") (pintype "bidirectional+no_connect"))
    )
    (net (code "300") (name "unconnected-(U14A-IO_L16N_T2_A15_D31_14-PadW17)") (class "Default")
      (node (ref "U14") (pin "W17") (pinfunction "IO_L16N_T2_A15_D31_14_W17") (pintype "bidirectional+no_connect"))
    )
    (net (code "301") (name "unconnected-(U14A-IO_L16P_T2_CSI_B_14-PadV17)") (class "Default")
      (node (ref "U14") (pin "V17") (pinfunction "IO_L16P_T2_CSI_B_14_V17") (pintype "bidirectional+no_connect"))
    )
    (net (code "302") (name "unconnected-(U14A-IO_L17P_T2_A14_D30_14-PadAA18)") (class "Default")
      (node (ref "U14") (pin "AA18") (pinfunction "IO_L17P_T2_A14_D30_14_AA18") (pintype "bidirectional+no_connect"))
    )
    (net (code "303") (name "unconnected-(U14A-IO_L19N_T3_A09_D25_VREF_14-PadR14)") (class "Default")
      (node (ref "U14") (pin "R14") (pinfunction "IO_L19N_T3_A09_D25_VREF_14_R14") (pintype "bidirectional+no_connect"))
    )
    (net (code "304") (name "unconnected-(U14A-IO_L20N_T3_A07_D23_14-PadT18)") (class "Default")
      (node (ref "U14") (pin "T18") (pinfunction "IO_L20N_T3_A07_D23_14_T18") (pintype "bidirectional+no_connect"))
    )
    (net (code "305") (name "unconnected-(U14A-IO_L20P_T3_A08_D24_14-PadR18)") (class "Default")
      (node (ref "U14") (pin "R18") (pinfunction "IO_L20P_T3_A08_D24_14_R18") (pintype "bidirectional+no_connect"))
    )
    (net (code "306") (name "unconnected-(U14A-IO_L21P_T3_DQS_14-PadN17)") (class "Default")
      (node (ref "U14") (pin "N17") (pinfunction "IO_L21P_T3_DQS_14_N17") (pintype "bidirectional+no_connect"))
    )
    (net (code "307") (name "unconnected-(U14D-IO_0_34-PadT3)") (class "Default")
      (node (ref "U14") (pin "T3") (pinfunction "IO_0_34_T3") (pintype "bidirectional+no_connect"))
    )
    (net (code "308") (name "unconnected-(U14D-IO_25_34-PadU7)") (class "Default")
      (node (ref "U14") (pin "U7") (pinfunction "IO_25_34_U7") (pintype "bidirectional+no_connect"))
    )
    (net (code "309") (name "unconnected-(U14E-IO_0_35-PadF4)") (class "Default")
      (node (ref "U14") (pin "F4") (pinfunction "IO_0_35_F4") (pintype "bidirectional+no_connect"))
    )
    (net (code "310") (name "unconnected-(U14E-IO_25_35-PadL6)") (class "Default")
      (node (ref "U14") (pin "L6") (pinfunction "IO_25_35_L6") (pintype "bidirectional+no_connect"))
    )
    (net (code "311") (name "unconnected-(U14E-IO_L2N_T0_AD12N_35-PadB2)") (class "Default")
      (node (ref "U14") (pin "B2") (pinfunction "IO_L2N_T0_AD12N_35_B2") (pintype "bidirectional+no_connect"))
    )
    (net (code "312") (name "unconnected-(U14E-IO_L11N_T1_SRCC_35-PadG3)") (class "Default")
      (node (ref "U14") (pin "G3") (pinfunction "IO_L11N_T1_SRCC_35_G3") (pintype "bidirectional+no_connect"))
    )
    (net (code "313") (name "unconnected-(U14E-IO_L11P_T1_SRCC_35-PadH3)") (class "Default")
      (node (ref "U14") (pin "H3") (pinfunction "IO_L11P_T1_SRCC_35_H3") (pintype "bidirectional+no_connect"))
    )
    (net (code "314") (name "unconnected-(U14L-NC-PadAA9)") (class "Default")
      (node (ref "U14") (pin "AA9") (pinfunction "NC_AA9") (pintype "passive+no_connect"))
    )
    (net (code "315") (name "unconnected-(U14L-NC-PadAA10)") (class "Default")
      (node (ref "U14") (pin "AA10") (pinfunction "NC_AA10") (pintype "passive+no_connect"))
    )
    (net (code "316") (name "unconnected-(U14L-NC-PadAA11)") (class "Default")
      (node (ref "U14") (pin "AA11") (pinfunction "NC_AA11") (pintype "passive+no_connect"))
    )
    (net (code "317") (name "unconnected-(U14L-NC-PadAA13)") (class "Default")
      (node (ref "U14") (pin "AA13") (pinfunction "NC_AA13") (pintype "passive+no_connect"))
    )
    (net (code "318") (name "unconnected-(U14L-NC-PadAA14)") (class "Default")
      (node (ref "U14") (pin "AA14") (pinfunction "NC_AA14") (pintype "passive+no_connect"))
    )
    (net (code "319") (name "unconnected-(U14L-NC-PadAA15)") (class "Default")
      (node (ref "U14") (pin "AA15") (pinfunction "NC_AA15") (pintype "passive+no_connect"))
    )
    (net (code "320") (name "unconnected-(U14L-NC-PadAA16)") (class "Default")
      (node (ref "U14") (pin "AA16") (pinfunction "NC_AA16") (pintype "passive+no_connect"))
    )
    (net (code "321") (name "unconnected-(U14L-NC-PadAB10)") (class "Default")
      (node (ref "U14") (pin "AB10") (pinfunction "NC_AB10") (pintype "passive+no_connect"))
    )
    (net (code "322") (name "unconnected-(U14L-NC-PadAB11)") (class "Default")
      (node (ref "U14") (pin "AB11") (pinfunction "NC_AB11") (pintype "passive+no_connect"))
    )
    (net (code "323") (name "unconnected-(U14L-NC-PadAB12)") (class "Default")
      (node (ref "U14") (pin "AB12") (pinfunction "NC_AB12") (pintype "passive+no_connect"))
    )
    (net (code "324") (name "unconnected-(U14L-NC-PadAB13)") (class "Default")
      (node (ref "U14") (pin "AB13") (pinfunction "NC_AB13") (pintype "passive+no_connect"))
    )
    (net (code "325") (name "unconnected-(U14L-NC-PadAB15)") (class "Default")
      (node (ref "U14") (pin "AB15") (pinfunction "NC_AB15") (pintype "passive+no_connect"))
    )
    (net (code "326") (name "unconnected-(U14L-NC-PadAB16)") (class "Default")
      (node (ref "U14") (pin "AB16") (pinfunction "NC_AB16") (pintype "passive+no_connect"))
    )
    (net (code "327") (name "unconnected-(U14L-NC-PadAB17)") (class "Default")
      (node (ref "U14") (pin "AB17") (pinfunction "NC_AB17") (pintype "passive+no_connect"))
    )
    (net (code "328") (name "unconnected-(U14L-NC-PadT14)") (class "Default")
      (node (ref "U14") (pin "T14") (pinfunction "NC_T14") (pintype "passive+no_connect"))
    )
    (net (code "329") (name "unconnected-(U14L-NC-PadT15)") (class "Default")
      (node (ref "U14") (pin "T15") (pinfunction "NC_T15") (pintype "passive+no_connect"))
    )
    (net (code "330") (name "unconnected-(U14L-NC-PadT16)") (class "Default")
      (node (ref "U14") (pin "T16") (pinfunction "NC_T16") (pintype "passive+no_connect"))
    )
    (net (code "331") (name "unconnected-(U14L-NC-PadU15)") (class "Default")
      (node (ref "U14") (pin "U15") (pinfunction "NC_U15") (pintype "passive+no_connect"))
    )
    (net (code "332") (name "unconnected-(U14L-NC-PadU16)") (class "Default")
      (node (ref "U14") (pin "U16") (pinfunction "NC_U16") (pintype "passive+no_connect"))
    )
    (net (code "333") (name "unconnected-(U14L-NC-PadV10)") (class "Default")
      (node (ref "U14") (pin "V10") (pinfunction "NC_V10") (pintype "passive+no_connect"))
    )
    (net (code "334") (name "unconnected-(U14L-NC-PadV13)") (class "Default")
      (node (ref "U14") (pin "V13") (pinfunction "NC_V13") (pintype "passive+no_connect"))
    )
    (net (code "335") (name "unconnected-(U14L-NC-PadV14)") (class "Default")
      (node (ref "U14") (pin "V14") (pinfunction "NC_V14") (pintype "passive+no_connect"))
    )
    (net (code "336") (name "unconnected-(U14L-NC-PadV15)") (class "Default")
      (node (ref "U14") (pin "V15") (pinfunction "NC_V15") (pintype "passive+no_connect"))
    )
    (net (code "337") (name "unconnected-(U14L-NC-PadW10)") (class "Default")
      (node (ref "U14") (pin "W10") (pinfunction "NC_W10") (pintype "passive+no_connect"))
    )
    (net (code "338") (name "unconnected-(U14L-NC-PadW11)") (class "Default")
      (node (ref "U14") (pin "W11") (pinfunction "NC_W11") (pintype "passive+no_connect"))
    )
    (net (code "339") (name "unconnected-(U14L-NC-PadW12)") (class "Default")
      (node (ref "U14") (pin "W12") (pinfunction "NC_W12") (pintype "passive+no_connect"))
    )
    (net (code "340") (name "unconnected-(U14L-NC-PadW14)") (class "Default")
      (node (ref "U14") (pin "W14") (pinfunction "NC_W14") (pintype "passive+no_connect"))
    )
    (net (code "341") (name "unconnected-(U14L-NC-PadW15)") (class "Default")
      (node (ref "U14") (pin "W15") (pinfunction "NC_W15") (pintype "passive+no_connect"))
    )
    (net (code "342") (name "unconnected-(U14L-NC-PadW16)") (class "Default")
      (node (ref "U14") (pin "W16") (pinfunction "NC_W16") (pintype "passive+no_connect"))
    )
    (net (code "343") (name "unconnected-(U14L-NC-PadY11)") (class "Default")
      (node (ref "U14") (pin "Y11") (pinfunction "NC_Y11") (pintype "passive+no_connect"))
    )
    (net (code "344") (name "unconnected-(U14L-NC-PadY12)") (class "Default")
      (node (ref "U14") (pin "Y12") (pinfunction "NC_Y12") (pintype "passive+no_connect"))
    )
    (net (code "345") (name "unconnected-(U14L-NC-PadY13)") (class "Default")
      (node (ref "U14") (pin "Y13") (pinfunction "NC_Y13") (pintype "passive+no_connect"))
    )
    (net (code "346") (name "unconnected-(U14L-NC-PadY14)") (class "Default")
      (node (ref "U14") (pin "Y14") (pinfunction "NC_Y14") (pintype "passive+no_connect"))
    )
    (net (code "347") (name "unconnected-(U14L-NC-PadY16)") (class "Default")
      (node (ref "U14") (pin "Y16") (pinfunction "NC_Y16") (pintype "passive+no_connect"))
    )
    (net (code "348") (name "unconnected-(U14L-NC-PadY17)") (class "Default")
      (node (ref "U14") (pin "Y17") (pinfunction "NC_Y17") (pintype "passive+no_connect"))
    )
    (net (code "349") (name "unconnected-(U16-NC-Pad2)") (class "Default")
      (node (ref "U16") (pin "2") (pinfunction "NC_2") (pintype "passive+no_connect"))
    )
  )
)
